# DAC.net
KiCad netlist of a schematic drawn in Altium Designer
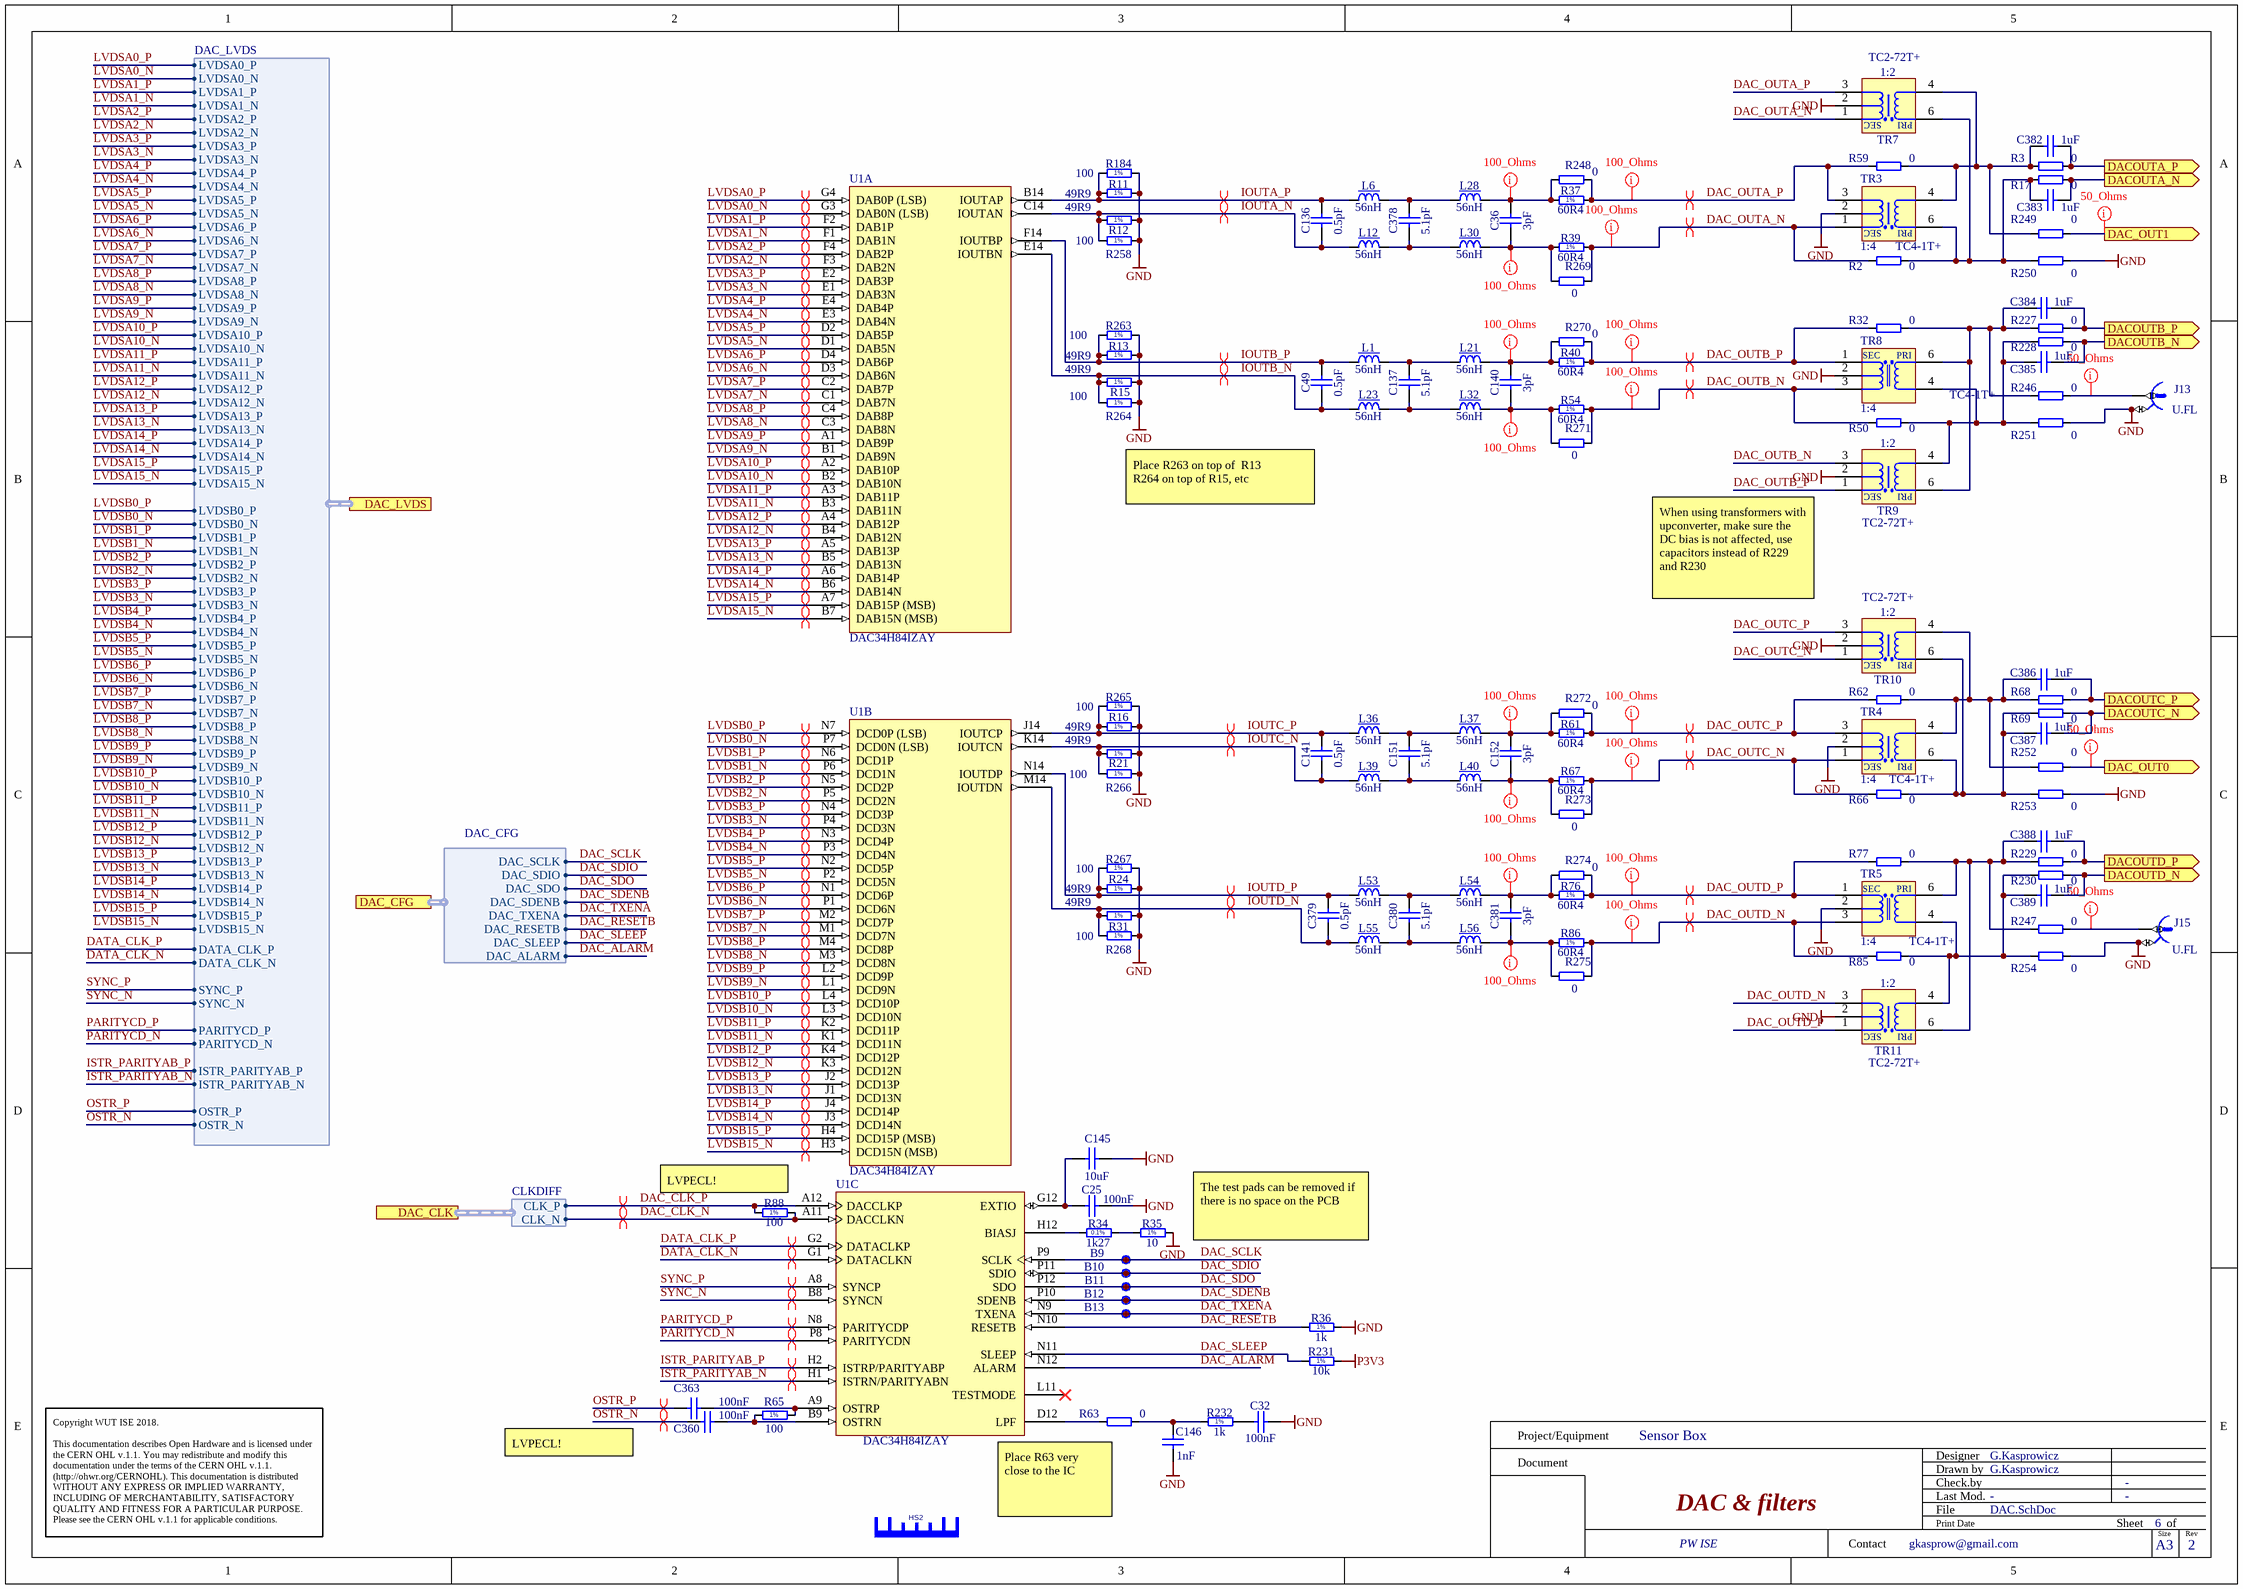
[diagram p0: DAC.SchDoc]

(export (version "E")
  (design (tool "Eeschema 10.0.6"))
  (components
    (comp (ref "B9")
      (value "SMD Pad")
      (footprint "C100")
      (description "Through Hole Pad")
      (fields (field (name "PART NUMBER") "SMD_PAD_D1MM") (field (name "AUTHOR") "CERN DEM JLC"))
      (libsource (lib "Eletro-mechanical") (part "Single SMD Pad (Round)"))
    )
    (comp (ref "B10")
      (value "SMD Pad")
      (footprint "C100")
      (description "Through Hole Pad")
      (fields (field (name "PART NUMBER") "SMD_PAD_D1MM") (field (name "AUTHOR") "CERN DEM JLC"))
      (libsource (lib "Eletro-mechanical") (part "Single SMD Pad (Round)"))
    )
    (comp (ref "B11")
      (value "SMD Pad")
      (footprint "C100")
      (description "Through Hole Pad")
      (fields (field (name "PART NUMBER") "SMD_PAD_D1MM") (field (name "AUTHOR") "CERN DEM JLC"))
      (libsource (lib "Eletro-mechanical") (part "Single SMD Pad (Round)"))
    )
    (comp (ref "B12")
      (value "SMD Pad")
      (footprint "C100")
      (description "Through Hole Pad")
      (fields (field (name "PART NUMBER") "SMD_PAD_D1MM") (field (name "AUTHOR") "CERN DEM JLC"))
      (libsource (lib "Eletro-mechanical") (part "Single SMD Pad (Round)"))
    )
    (comp (ref "B13")
      (value "SMD Pad")
      (footprint "C100")
      (description "Through Hole Pad")
      (fields (field (name "PART NUMBER") "SMD_PAD_D1MM") (field (name "AUTHOR") "CERN DEM JLC"))
      (libsource (lib "Eletro-mechanical") (part "Single SMD Pad (Round)"))
    )
    (comp (ref "C25")
      (value "100nF")
      (footprint "CAPC1005X55N")
      (description "Non-polarised capacitor")
      (fields
        (field (name "PART NUMBER") "CC0402_100NF_16V_10%_X5R")
        (field (name "VOLTAGE") "16V")
        (field (name "AUTHOR") "CERN DEM JLC")
      )
      (libsource (lib "Capacitors") (part "Capacitor - non polarized"))
    )
    (comp (ref "C32")
      (value "100nF")
      (footprint "CAPC1608X90N")
      (description "Non-polarised capacitor")
      (fields
        (field (name "PART NUMBER") "CC0603_100NF_100V_10%_X7R")
        (field (name "VOLTAGE") "100V")
        (field (name "AUTHOR") "CERN DEM JLC")
      )
      (libsource (lib "Capacitors") (part "Capacitor - non polarized"))
    )
    (comp (ref "C36")
      (value "3pF")
      (footprint "CAPC1608X87N")
      (description "Non-polarised capacitor")
      (libsource (lib "Capacitors") (part "CC0603_3pF_50V_0,1pF_NP0"))
    )
    (comp (ref "C49")
      (value "0.5pF")
      (footprint "CAPC1608X87N")
      (description "Non-polarised capacitor")
      (libsource (lib "Capacitors") (part "CC0603_0.5pF_50V_0,05pF_NP0"))
    )
    (comp (ref "C136")
      (value "0.5pF")
      (footprint "CAPC1608X87N")
      (description "Non-polarised capacitor")
      (libsource (lib "Capacitors") (part "CC0603_0.5pF_50V_0,05pF_NP0"))
    )
    (comp (ref "C137")
      (value "5.1pF")
      (footprint "CAPC1608X87N")
      (description "Non-polarised capacitor")
      (libsource (lib "Capacitors") (part "CC0603_5.1pF_50V_0.1pF_NP0"))
    )
    (comp (ref "C140")
      (value "3pF")
      (footprint "CAPC1608X87N")
      (description "Non-polarised capacitor")
      (libsource (lib "Capacitors") (part "CC0603_3pF_50V_0,1pF_NP0"))
    )
    (comp (ref "C141")
      (value "0.5pF")
      (footprint "CAPC1608X87N")
      (description "Non-polarised capacitor")
      (libsource (lib "Capacitors") (part "CC0603_0.5pF_50V_0,05pF_NP0"))
    )
    (comp (ref "C145")
      (value "10uF")
      (footprint "CAPC2012X95N")
      (description "Non-polarised capacitor")
      (fields
        (field (name "PART NUMBER") "CC0805_10UF_25V_10%_X5R")
        (field (name "VOLTAGE") "25V")
        (field (name "AUTHOR") "CERN DEM JLC")
      )
      (libsource (lib "Capacitors") (part "Capacitor - non polarized"))
    )
    (comp (ref "C146")
      (value "1nF")
      (footprint "CAPC1608X90N")
      (description "Non-polarised capacitor")
      (fields
        (field (name "PART NUMBER") "CC0603_1NF_50V_1%_NP0")
        (field (name "VOLTAGE") "50V")
        (field (name "AUTHOR") "CERN DEM JLC")
      )
      (libsource (lib "Capacitors") (part "Capacitor - non polarized"))
    )
    (comp (ref "C151")
      (value "5.1pF")
      (footprint "CAPC1608X87N")
      (description "Non-polarised capacitor")
      (libsource (lib "Capacitors") (part "CC0603_5.1pF_50V_0.1pF_NP0"))
    )
    (comp (ref "C152")
      (value "3pF")
      (footprint "CAPC1608X87N")
      (description "Non-polarised capacitor")
      (libsource (lib "Capacitors") (part "CC0603_3pF_50V_0,1pF_NP0"))
    )
    (comp (ref "C360")
      (value "100nF")
      (footprint "CAPC1005X55N")
      (description "Non-polarised capacitor")
      (fields
        (field (name "PART NUMBER") "CC0402_100NF_16V_10%_X5R")
        (field (name "VOLTAGE") "16V")
        (field (name "AUTHOR") "CERN DEM JLC")
      )
      (libsource (lib "Capacitors") (part "Capacitor - non polarized"))
    )
    (comp (ref "C363")
      (value "100nF")
      (footprint "CAPC1005X55N")
      (description "Non-polarised capacitor")
      (fields
        (field (name "PART NUMBER") "CC0402_100NF_16V_10%_X5R")
        (field (name "VOLTAGE") "16V")
        (field (name "AUTHOR") "CERN DEM JLC")
      )
      (libsource (lib "Capacitors") (part "Capacitor - non polarized"))
    )
    (comp (ref "C378")
      (value "5.1pF")
      (footprint "CAPC1608X87N")
      (description "Non-polarised capacitor")
      (libsource (lib "Capacitors") (part "CC0603_5.1pF_50V_0.1pF_NP0"))
    )
    (comp (ref "C379")
      (value "0.5pF")
      (footprint "CAPC1608X87N")
      (description "Non-polarised capacitor")
      (libsource (lib "Capacitors") (part "CC0603_0.5pF_50V_0,05pF_NP0"))
    )
    (comp (ref "C380")
      (value "5.1pF")
      (footprint "CAPC1608X87N")
      (description "Non-polarised capacitor")
      (libsource (lib "Capacitors") (part "CC0603_5.1pF_50V_0.1pF_NP0"))
    )
    (comp (ref "C381")
      (value "3pF")
      (footprint "CAPC1608X87N")
      (description "Non-polarised capacitor")
      (libsource (lib "Capacitors") (part "CC0603_3pF_50V_0,1pF_NP0"))
    )
    (comp (ref "C382")
      (value "1uF")
      (footprint "CAPC1005X55N")
      (description "Non-polarised capacitor")
      (fields
        (field (name "PART NUMBER") "CC0402_1UF_16V_10%_X5R")
        (field (name "VOLTAGE") "16V")
        (field (name "AUTHOR") "CERN DEM JLC")
      )
      (libsource (lib "Capacitors") (part "Capacitor - non polarized"))
    )
    (comp (ref "C383")
      (value "1uF")
      (footprint "CAPC1005X55N")
      (description "Non-polarised capacitor")
      (fields
        (field (name "PART NUMBER") "CC0402_1UF_16V_10%_X5R")
        (field (name "VOLTAGE") "16V")
        (field (name "AUTHOR") "CERN DEM JLC")
      )
      (libsource (lib "Capacitors") (part "Capacitor - non polarized"))
    )
    (comp (ref "C384")
      (value "1uF")
      (footprint "CAPC1005X55N")
      (description "Non-polarised capacitor")
      (fields
        (field (name "PART NUMBER") "CC0402_1UF_16V_10%_X5R")
        (field (name "VOLTAGE") "16V")
        (field (name "AUTHOR") "CERN DEM JLC")
      )
      (libsource (lib "Capacitors") (part "Capacitor - non polarized"))
    )
    (comp (ref "C385")
      (value "1uF")
      (footprint "CAPC1005X55N")
      (description "Non-polarised capacitor")
      (fields
        (field (name "PART NUMBER") "CC0402_1UF_16V_10%_X5R")
        (field (name "VOLTAGE") "16V")
        (field (name "AUTHOR") "CERN DEM JLC")
      )
      (libsource (lib "Capacitors") (part "Capacitor - non polarized"))
    )
    (comp (ref "C386")
      (value "1uF")
      (footprint "CAPC1005X55N")
      (description "Non-polarised capacitor")
      (fields
        (field (name "PART NUMBER") "CC0402_1UF_16V_10%_X5R")
        (field (name "VOLTAGE") "16V")
        (field (name "AUTHOR") "CERN DEM JLC")
      )
      (libsource (lib "Capacitors") (part "Capacitor - non polarized"))
    )
    (comp (ref "C387")
      (value "1uF")
      (footprint "CAPC1005X55N")
      (description "Non-polarised capacitor")
      (fields
        (field (name "PART NUMBER") "CC0402_1UF_16V_10%_X5R")
        (field (name "VOLTAGE") "16V")
        (field (name "AUTHOR") "CERN DEM JLC")
      )
      (libsource (lib "Capacitors") (part "Capacitor - non polarized"))
    )
    (comp (ref "C388")
      (value "1uF")
      (footprint "CAPC1005X55N")
      (description "Non-polarised capacitor")
      (fields
        (field (name "PART NUMBER") "CC0402_1UF_16V_10%_X5R")
        (field (name "VOLTAGE") "16V")
        (field (name "AUTHOR") "CERN DEM JLC")
      )
      (libsource (lib "Capacitors") (part "Capacitor - non polarized"))
    )
    (comp (ref "C389")
      (value "1uF")
      (footprint "CAPC1005X55N")
      (description "Non-polarised capacitor")
      (fields
        (field (name "PART NUMBER") "CC0402_1UF_16V_10%_X5R")
        (field (name "VOLTAGE") "16V")
        (field (name "AUTHOR") "CERN DEM JLC")
      )
      (libsource (lib "Capacitors") (part "Capacitor - non polarized"))
    )
    (comp (ref "HS2")
      (value "Heat Sink No Pad")
      (footprint "HSINK_HSB03-121218")
      (description "Rth: 27.5K/W - L 12mm x W 12mm x H 18mm Black Anodized Heatsinks for BGA")
      (fields
        (field (name "PART NUMBER") "HSB03-121218")
        (field (name "MANUFACTURER") "CUI")
        (field (name "AUTHOR") "GK")
      )
      (libsource (lib "Mechanical") (part "HEAT_SINK_BGA_12x12x18"))
    )
    (comp (ref "J13")
      (value "U.FL")
      (footprint "HIROSE_U.FL-R-SMT-1(10)")
      (fields
        (field (name "MANUFACTURER") "HIROSE (HRS)")
        (field (name "MANUFACTURER PART NUMBER") "U.FL-R-SMT-1(10)")
        (field (name "PART NUMBER") "HIROSE_U.FL-R-SMT-1(10)")
        (field (name "AUTHOR") "CERN DEM JLC")
      )
      (libsource (lib "Connectors") (part "Coax_1Male_1Shield"))
    )
    (comp (ref "J15")
      (value "U.FL")
      (footprint "HIROSE_U.FL-R-SMT-1(10)")
      (fields
        (field (name "MANUFACTURER") "HIROSE (HRS)")
        (field (name "MANUFACTURER PART NUMBER") "U.FL-R-SMT-1(10)")
        (field (name "PART NUMBER") "HIROSE_U.FL-R-SMT-1(10)")
        (field (name "AUTHOR") "CERN DEM JLC")
      )
      (libsource (lib "Connectors") (part "Coax_1Male_1Shield"))
    )
    (comp (ref "L1")
      (value "56nH")
      (footprint "IND_MURATA_LQW18AS_0Z")
      (description "Inductor With Core")
      (fields
        (field (name "PART NUMBER") "IND0603_56NH_2%_MURATA_LQW18AS56NG0ZD")
        (field (name "POWER") "600mA")
        (field (name "AUTHOR") "CERN DEM BC")
      )
      (libsource (lib "Inductors & Transformers") (part "Inductor With Magnetic core"))
    )
    (comp (ref "L6")
      (value "56nH")
      (footprint "IND_MURATA_LQW18AS_0Z")
      (description "Inductor With Core")
      (fields
        (field (name "PART NUMBER") "IND0603_56NH_2%_MURATA_LQW18AS56NG0ZD")
        (field (name "POWER") "600mA")
        (field (name "AUTHOR") "CERN DEM BC")
      )
      (libsource (lib "Inductors & Transformers") (part "Inductor With Magnetic core"))
    )
    (comp (ref "L12")
      (value "56nH")
      (footprint "IND_MURATA_LQW18AS_0Z")
      (description "Inductor With Core")
      (fields
        (field (name "PART NUMBER") "IND0603_56NH_2%_MURATA_LQW18AS56NG0ZD")
        (field (name "POWER") "600mA")
        (field (name "AUTHOR") "CERN DEM BC")
      )
      (libsource (lib "Inductors & Transformers") (part "Inductor With Magnetic core"))
    )
    (comp (ref "L21")
      (value "56nH")
      (footprint "IND_MURATA_LQW18AS_0Z")
      (description "Inductor With Core")
      (fields
        (field (name "PART NUMBER") "IND0603_56NH_2%_MURATA_LQW18AS56NG0ZD")
        (field (name "POWER") "600mA")
        (field (name "AUTHOR") "CERN DEM BC")
      )
      (libsource (lib "Inductors & Transformers") (part "Inductor With Magnetic core"))
    )
    (comp (ref "L23")
      (value "56nH")
      (footprint "IND_MURATA_LQW18AS_0Z")
      (description "Inductor With Core")
      (fields
        (field (name "PART NUMBER") "IND0603_56NH_2%_MURATA_LQW18AS56NG0ZD")
        (field (name "POWER") "600mA")
        (field (name "AUTHOR") "CERN DEM BC")
      )
      (libsource (lib "Inductors & Transformers") (part "Inductor With Magnetic core"))
    )
    (comp (ref "L28")
      (value "56nH")
      (footprint "IND_MURATA_LQW18AS_0Z")
      (description "Inductor With Core")
      (fields
        (field (name "PART NUMBER") "IND0603_56NH_2%_MURATA_LQW18AS56NG0ZD")
        (field (name "POWER") "600mA")
        (field (name "AUTHOR") "CERN DEM BC")
      )
      (libsource (lib "Inductors & Transformers") (part "Inductor With Magnetic core"))
    )
    (comp (ref "L30")
      (value "56nH")
      (footprint "IND_MURATA_LQW18AS_0Z")
      (description "Inductor With Core")
      (fields
        (field (name "PART NUMBER") "IND0603_56NH_2%_MURATA_LQW18AS56NG0ZD")
        (field (name "POWER") "600mA")
        (field (name "AUTHOR") "CERN DEM BC")
      )
      (libsource (lib "Inductors & Transformers") (part "Inductor With Magnetic core"))
    )
    (comp (ref "L32")
      (value "56nH")
      (footprint "IND_MURATA_LQW18AS_0Z")
      (description "Inductor With Core")
      (fields
        (field (name "PART NUMBER") "IND0603_56NH_2%_MURATA_LQW18AS56NG0ZD")
        (field (name "POWER") "600mA")
        (field (name "AUTHOR") "CERN DEM BC")
      )
      (libsource (lib "Inductors & Transformers") (part "Inductor With Magnetic core"))
    )
    (comp (ref "L36")
      (value "56nH")
      (footprint "IND_MURATA_LQW18AS_0Z")
      (description "Inductor With Core")
      (fields
        (field (name "PART NUMBER") "IND0603_56NH_2%_MURATA_LQW18AS56NG0ZD")
        (field (name "POWER") "600mA")
        (field (name "AUTHOR") "CERN DEM BC")
      )
      (libsource (lib "Inductors & Transformers") (part "Inductor With Magnetic core"))
    )
    (comp (ref "L37")
      (value "56nH")
      (footprint "IND_MURATA_LQW18AS_0Z")
      (description "Inductor With Core")
      (fields
        (field (name "PART NUMBER") "IND0603_56NH_2%_MURATA_LQW18AS56NG0ZD")
        (field (name "POWER") "600mA")
        (field (name "AUTHOR") "CERN DEM BC")
      )
      (libsource (lib "Inductors & Transformers") (part "Inductor With Magnetic core"))
    )
    (comp (ref "L39")
      (value "56nH")
      (footprint "IND_MURATA_LQW18AS_0Z")
      (description "Inductor With Core")
      (fields
        (field (name "PART NUMBER") "IND0603_56NH_2%_MURATA_LQW18AS56NG0ZD")
        (field (name "POWER") "600mA")
        (field (name "AUTHOR") "CERN DEM BC")
      )
      (libsource (lib "Inductors & Transformers") (part "Inductor With Magnetic core"))
    )
    (comp (ref "L40")
      (value "56nH")
      (footprint "IND_MURATA_LQW18AS_0Z")
      (description "Inductor With Core")
      (fields
        (field (name "PART NUMBER") "IND0603_56NH_2%_MURATA_LQW18AS56NG0ZD")
        (field (name "POWER") "600mA")
        (field (name "AUTHOR") "CERN DEM BC")
      )
      (libsource (lib "Inductors & Transformers") (part "Inductor With Magnetic core"))
    )
    (comp (ref "L53")
      (value "56nH")
      (footprint "IND_MURATA_LQW18AS_0Z")
      (description "Inductor With Core")
      (fields
        (field (name "PART NUMBER") "IND0603_56NH_2%_MURATA_LQW18AS56NG0ZD")
        (field (name "POWER") "600mA")
        (field (name "AUTHOR") "CERN DEM BC")
      )
      (libsource (lib "Inductors & Transformers") (part "Inductor With Magnetic core"))
    )
    (comp (ref "L54")
      (value "56nH")
      (footprint "IND_MURATA_LQW18AS_0Z")
      (description "Inductor With Core")
      (fields
        (field (name "PART NUMBER") "IND0603_56NH_2%_MURATA_LQW18AS56NG0ZD")
        (field (name "POWER") "600mA")
        (field (name "AUTHOR") "CERN DEM BC")
      )
      (libsource (lib "Inductors & Transformers") (part "Inductor With Magnetic core"))
    )
    (comp (ref "L55")
      (value "56nH")
      (footprint "IND_MURATA_LQW18AS_0Z")
      (description "Inductor With Core")
      (fields
        (field (name "PART NUMBER") "IND0603_56NH_2%_MURATA_LQW18AS56NG0ZD")
        (field (name "POWER") "600mA")
        (field (name "AUTHOR") "CERN DEM BC")
      )
      (libsource (lib "Inductors & Transformers") (part "Inductor With Magnetic core"))
    )
    (comp (ref "L56")
      (value "56nH")
      (footprint "IND_MURATA_LQW18AS_0Z")
      (description "Inductor With Core")
      (fields
        (field (name "PART NUMBER") "IND0603_56NH_2%_MURATA_LQW18AS56NG0ZD")
        (field (name "POWER") "600mA")
        (field (name "AUTHOR") "CERN DEM BC")
      )
      (libsource (lib "Inductors & Transformers") (part "Inductor With Magnetic core"))
    )
    (comp (ref "R2")
      (value "0")
      (footprint "RESC1005X40N")
      (description "Resistor")
      (fields
        (field (name "PART NUMBER") "R0402_0R_JUMPER")
        (field (name "MANUFACTURER") "GENERIC")
        (field (name "AUTHOR") "CERN DEM JLC")
      )
      (libsource (lib "Resistors") (part "Resistor"))
    )
    (comp (ref "R3")
      (value "0")
      (footprint "RESC1005X40N")
      (description "Resistor")
      (fields
        (field (name "PART NUMBER") "R0402_0R_JUMPER")
        (field (name "MANUFACTURER") "GENERIC")
        (field (name "AUTHOR") "CERN DEM JLC")
      )
      (libsource (lib "Resistors") (part "Resistor"))
    )
    (comp (ref "R11")
      (value "49R9")
      (footprint "RESC1005X40N")
      (description "Resistor - 1%")
      (fields
        (field (name "PART NUMBER") "R0402_49R9_1%_0.0625W_100PPM")
        (field (name "POWER") "0.0625W")
        (field (name "AUTHOR") "CERN DEM JLC")
      )
      (libsource (lib "Resistors") (part "Resistor - 1%"))
    )
    (comp (ref "R12")
      (value "49R9")
      (footprint "RESC1005X40N")
      (description "Resistor - 1%")
      (fields
        (field (name "PART NUMBER") "R0402_49R9_1%_0.0625W_100PPM")
        (field (name "POWER") "0.0625W")
        (field (name "AUTHOR") "CERN DEM JLC")
      )
      (libsource (lib "Resistors") (part "Resistor - 1%"))
    )
    (comp (ref "R13")
      (value "49R9")
      (footprint "RESC1005X40N")
      (description "Resistor - 1%")
      (fields
        (field (name "PART NUMBER") "R0402_49R9_1%_0.0625W_100PPM")
        (field (name "POWER") "0.0625W")
        (field (name "AUTHOR") "CERN DEM JLC")
      )
      (libsource (lib "Resistors") (part "Resistor - 1%"))
    )
    (comp (ref "R15")
      (value "49R9")
      (footprint "RESC1005X40N")
      (description "Resistor - 1%")
      (fields
        (field (name "PART NUMBER") "R0402_49R9_1%_0.0625W_100PPM")
        (field (name "POWER") "0.0625W")
        (field (name "AUTHOR") "CERN DEM JLC")
      )
      (libsource (lib "Resistors") (part "Resistor - 1%"))
    )
    (comp (ref "R16")
      (value "49R9")
      (footprint "RESC1005X40N")
      (description "Resistor - 1%")
      (fields
        (field (name "PART NUMBER") "R0402_49R9_1%_0.0625W_100PPM")
        (field (name "POWER") "0.0625W")
        (field (name "AUTHOR") "CERN DEM JLC")
      )
      (libsource (lib "Resistors") (part "Resistor - 1%"))
    )
    (comp (ref "R17")
      (value "0")
      (footprint "RESC1005X40N")
      (description "Resistor")
      (fields
        (field (name "PART NUMBER") "R0402_0R_JUMPER")
        (field (name "MANUFACTURER") "GENERIC")
        (field (name "AUTHOR") "CERN DEM JLC")
      )
      (libsource (lib "Resistors") (part "Resistor"))
    )
    (comp (ref "R21")
      (value "49R9")
      (footprint "RESC1005X40N")
      (description "Resistor - 1%")
      (fields
        (field (name "PART NUMBER") "R0402_49R9_1%_0.0625W_100PPM")
        (field (name "POWER") "0.0625W")
        (field (name "AUTHOR") "CERN DEM JLC")
      )
      (libsource (lib "Resistors") (part "Resistor - 1%"))
    )
    (comp (ref "R24")
      (value "49R9")
      (footprint "RESC1005X40N")
      (description "Resistor - 1%")
      (fields
        (field (name "PART NUMBER") "R0402_49R9_1%_0.0625W_100PPM")
        (field (name "POWER") "0.0625W")
        (field (name "AUTHOR") "CERN DEM JLC")
      )
      (libsource (lib "Resistors") (part "Resistor - 1%"))
    )
    (comp (ref "R31")
      (value "49R9")
      (footprint "RESC1005X40N")
      (description "Resistor - 1%")
      (fields
        (field (name "PART NUMBER") "R0402_49R9_1%_0.0625W_100PPM")
        (field (name "POWER") "0.0625W")
        (field (name "AUTHOR") "CERN DEM JLC")
      )
      (libsource (lib "Resistors") (part "Resistor - 1%"))
    )
    (comp (ref "R32")
      (value "0")
      (footprint "RESC1005X40N")
      (description "Resistor")
      (fields
        (field (name "PART NUMBER") "R0402_0R_JUMPER")
        (field (name "MANUFACTURER") "GENERIC")
        (field (name "AUTHOR") "CERN DEM JLC")
      )
      (libsource (lib "Resistors") (part "Resistor"))
    )
    (comp (ref "R34")
      (value "1k27")
      (footprint "RESC1608X55N")
      (description "Resistor - 0.1%")
      (fields
        (field (name "PART NUMBER") "R0603_1K27_0.1%_0.063W_10PPM")
        (field (name "POWER") "0.063W")
        (field (name "AUTHOR") "CERN DEM JLC")
      )
      (libsource (lib "Resistors") (part "Resistor - 0.1%"))
    )
    (comp (ref "R35")
      (value "10")
      (footprint "RESC1005X40N")
      (description "Resistor - 1%")
      (fields
        (field (name "PART NUMBER") "R0402_10R_1%_0.0625W_200PPM")
        (field (name "POWER") "0.0625W")
        (field (name "AUTHOR") "CERN DEM JLC")
      )
      (libsource (lib "Resistors") (part "Resistor - 1%"))
    )
    (comp (ref "R36")
      (value "1k")
      (footprint "RESC1608X55N")
      (description "Resistor - 1%")
      (fields
        (field (name "PART NUMBER") "R0603_1K_1%_0.1W_100PPM")
        (field (name "POWER") "0.1W")
        (field (name "AUTHOR") "CERN DEM JLC")
      )
      (libsource (lib "Resistors") (part "Resistor - 1%"))
    )
    (comp (ref "R37")
      (value "60R4")
      (footprint "RESC1005X40N")
      (description "Resistor - 1%")
      (fields
        (field (name "PART NUMBER") "R0402_60R4_1%_0.0625W_100PPM")
        (field (name "POWER") "0.0625W")
        (field (name "AUTHOR") "GK")
      )
      (libsource (lib "Passives_RC") (part "R0402_60R4_1%_0.0625W_100PPM"))
    )
    (comp (ref "R39")
      (value "60R4")
      (footprint "RESC1005X40N")
      (description "Resistor - 1%")
      (fields
        (field (name "PART NUMBER") "R0402_60R4_1%_0.0625W_100PPM")
        (field (name "POWER") "0.0625W")
        (field (name "AUTHOR") "GK")
      )
      (libsource (lib "Passives_RC") (part "R0402_60R4_1%_0.0625W_100PPM"))
    )
    (comp (ref "R40")
      (value "60R4")
      (footprint "RESC1005X40N")
      (description "Resistor - 1%")
      (fields
        (field (name "PART NUMBER") "R0402_60R4_1%_0.0625W_100PPM")
        (field (name "POWER") "0.0625W")
        (field (name "AUTHOR") "GK")
      )
      (libsource (lib "Passives_RC") (part "R0402_60R4_1%_0.0625W_100PPM"))
    )
    (comp (ref "R50")
      (value "0")
      (footprint "RESC1005X40N")
      (description "Resistor")
      (fields
        (field (name "PART NUMBER") "R0402_0R_JUMPER")
        (field (name "MANUFACTURER") "GENERIC")
        (field (name "AUTHOR") "CERN DEM JLC")
      )
      (libsource (lib "Resistors") (part "Resistor"))
    )
    (comp (ref "R54")
      (value "60R4")
      (footprint "RESC1005X40N")
      (description "Resistor - 1%")
      (fields
        (field (name "PART NUMBER") "R0402_60R4_1%_0.0625W_100PPM")
        (field (name "POWER") "0.0625W")
        (field (name "AUTHOR") "GK")
      )
      (libsource (lib "Passives_RC") (part "R0402_60R4_1%_0.0625W_100PPM"))
    )
    (comp (ref "R59")
      (value "0")
      (footprint "RESC1005X40N")
      (description "Resistor")
      (fields
        (field (name "PART NUMBER") "R0402_0R_JUMPER")
        (field (name "MANUFACTURER") "GENERIC")
        (field (name "AUTHOR") "CERN DEM JLC")
      )
      (libsource (lib "Resistors") (part "Resistor"))
    )
    (comp (ref "R61")
      (value "60R4")
      (footprint "RESC1005X40N")
      (description "Resistor - 1%")
      (fields
        (field (name "PART NUMBER") "R0402_60R4_1%_0.0625W_100PPM")
        (field (name "POWER") "0.0625W")
        (field (name "AUTHOR") "GK")
      )
      (libsource (lib "Passives_RC") (part "R0402_60R4_1%_0.0625W_100PPM"))
    )
    (comp (ref "R62")
      (value "0")
      (footprint "RESC1005X40N")
      (description "Resistor")
      (fields
        (field (name "PART NUMBER") "R0402_0R_JUMPER")
        (field (name "MANUFACTURER") "GENERIC")
        (field (name "AUTHOR") "CERN DEM JLC")
      )
      (libsource (lib "Resistors") (part "Resistor"))
    )
    (comp (ref "R63")
      (value "0")
      (footprint "RESC1005X40N")
      (description "Resistor")
      (fields
        (field (name "PART NUMBER") "R0402_0R_JUMPER")
        (field (name "MANUFACTURER") "GENERIC")
        (field (name "AUTHOR") "CERN DEM JLC")
      )
      (libsource (lib "Resistors") (part "Resistor"))
    )
    (comp (ref "R65")
      (value "100")
      (footprint "RESC0603X28N")
      (description "Resistor - 1%")
      (fields
        (field (name "PART NUMBER") "R0201_100R_1%_0.05W_200PPM")
        (field (name "POWER") "0.05W")
        (field (name "AUTHOR") "CERN DEM JLC")
      )
      (libsource (lib "Resistors") (part "Resistor - 1%"))
    )
    (comp (ref "R66")
      (value "0")
      (footprint "RESC1005X40N")
      (description "Resistor")
      (fields
        (field (name "PART NUMBER") "R0402_0R_JUMPER")
        (field (name "MANUFACTURER") "GENERIC")
        (field (name "AUTHOR") "CERN DEM JLC")
      )
      (libsource (lib "Resistors") (part "Resistor"))
    )
    (comp (ref "R67")
      (value "60R4")
      (footprint "RESC1005X40N")
      (description "Resistor - 1%")
      (fields
        (field (name "PART NUMBER") "R0402_60R4_1%_0.0625W_100PPM")
        (field (name "POWER") "0.0625W")
        (field (name "AUTHOR") "GK")
      )
      (libsource (lib "Passives_RC") (part "R0402_60R4_1%_0.0625W_100PPM"))
    )
    (comp (ref "R68")
      (value "0")
      (footprint "RESC1005X40N")
      (description "Resistor")
      (fields
        (field (name "PART NUMBER") "R0402_0R_JUMPER")
        (field (name "MANUFACTURER") "GENERIC")
        (field (name "AUTHOR") "CERN DEM JLC")
      )
      (libsource (lib "Resistors") (part "Resistor"))
    )
    (comp (ref "R69")
      (value "0")
      (footprint "RESC1005X40N")
      (description "Resistor")
      (fields
        (field (name "PART NUMBER") "R0402_0R_JUMPER")
        (field (name "MANUFACTURER") "GENERIC")
        (field (name "AUTHOR") "CERN DEM JLC")
      )
      (libsource (lib "Resistors") (part "Resistor"))
    )
    (comp (ref "R76")
      (value "60R4")
      (footprint "RESC1005X40N")
      (description "Resistor - 1%")
      (fields
        (field (name "PART NUMBER") "R0402_60R4_1%_0.0625W_100PPM")
        (field (name "POWER") "0.0625W")
        (field (name "AUTHOR") "GK")
      )
      (libsource (lib "Passives_RC") (part "R0402_60R4_1%_0.0625W_100PPM"))
    )
    (comp (ref "R77")
      (value "0")
      (footprint "RESC1005X40N")
      (description "Resistor")
      (fields
        (field (name "PART NUMBER") "R0402_0R_JUMPER")
        (field (name "MANUFACTURER") "GENERIC")
        (field (name "AUTHOR") "CERN DEM JLC")
      )
      (libsource (lib "Resistors") (part "Resistor"))
    )
    (comp (ref "R85")
      (value "0")
      (footprint "RESC1005X40N")
      (description "Resistor")
      (fields
        (field (name "PART NUMBER") "R0402_0R_JUMPER")
        (field (name "MANUFACTURER") "GENERIC")
        (field (name "AUTHOR") "CERN DEM JLC")
      )
      (libsource (lib "Resistors") (part "Resistor"))
    )
    (comp (ref "R86")
      (value "60R4")
      (footprint "RESC1005X40N")
      (description "Resistor - 1%")
      (fields
        (field (name "PART NUMBER") "R0402_60R4_1%_0.0625W_100PPM")
        (field (name "POWER") "0.0625W")
        (field (name "AUTHOR") "GK")
      )
      (libsource (lib "Passives_RC") (part "R0402_60R4_1%_0.0625W_100PPM"))
    )
    (comp (ref "R88")
      (value "100")
      (footprint "RESC0603X28N")
      (description "Resistor - 1%")
      (fields
        (field (name "PART NUMBER") "R0201_100R_1%_0.05W_200PPM")
        (field (name "POWER") "0.05W")
        (field (name "AUTHOR") "CERN DEM JLC")
      )
      (libsource (lib "Resistors") (part "Resistor - 1%"))
    )
    (comp (ref "R184")
      (value "100")
      (footprint "RESC1005X40N")
      (description "Resistor - 1%")
      (fields
        (field (name "PART NUMBER") "R0402_100R_1%_0.1W_100PPM")
        (field (name "POWER") "0.1W")
        (field (name "AUTHOR") "CERN DEM JLC")
      )
      (libsource (lib "Resistors") (part "Resistor - 1%"))
    )
    (comp (ref "R227")
      (value "0")
      (footprint "RESC1005X40N")
      (description "Resistor")
      (fields
        (field (name "PART NUMBER") "R0402_0R_JUMPER")
        (field (name "MANUFACTURER") "GENERIC")
        (field (name "AUTHOR") "CERN DEM JLC")
      )
      (libsource (lib "Resistors") (part "Resistor"))
    )
    (comp (ref "R228")
      (value "0")
      (footprint "RESC1005X40N")
      (description "Resistor")
      (fields
        (field (name "PART NUMBER") "R0402_0R_JUMPER")
        (field (name "MANUFACTURER") "GENERIC")
        (field (name "AUTHOR") "CERN DEM JLC")
      )
      (libsource (lib "Resistors") (part "Resistor"))
    )
    (comp (ref "R229")
      (value "0")
      (footprint "RESC1005X40N")
      (description "Resistor")
      (fields
        (field (name "PART NUMBER") "R0402_0R_JUMPER")
        (field (name "MANUFACTURER") "GENERIC")
        (field (name "AUTHOR") "CERN DEM JLC")
      )
      (libsource (lib "Resistors") (part "Resistor"))
    )
    (comp (ref "R230")
      (value "0")
      (footprint "RESC1005X40N")
      (description "Resistor")
      (fields
        (field (name "PART NUMBER") "R0402_0R_JUMPER")
        (field (name "MANUFACTURER") "GENERIC")
        (field (name "AUTHOR") "CERN DEM JLC")
      )
      (libsource (lib "Resistors") (part "Resistor"))
    )
    (comp (ref "R231")
      (value "10k")
      (footprint "RESC1608X55N")
      (description "Resistor - 1%")
      (fields
        (field (name "PART NUMBER") "R0603_10K_1%_0.1W_100PPM")
        (field (name "POWER") "0.1W")
        (field (name "AUTHOR") "CERN DEM JLC")
      )
      (libsource (lib "Resistors") (part "Resistor - 1%"))
    )
    (comp (ref "R232")
      (value "1k")
      (footprint "RESC1608X55N")
      (description "Resistor - 1%")
      (fields
        (field (name "PART NUMBER") "R0603_1K_1%_0.1W_100PPM")
        (field (name "POWER") "0.1W")
        (field (name "AUTHOR") "CERN DEM JLC")
      )
      (libsource (lib "Resistors") (part "Resistor - 1%"))
    )
    (comp (ref "R246")
      (value "0")
      (footprint "RESC1005X40N")
      (description "Resistor")
      (fields
        (field (name "PART NUMBER") "R0402_0R_JUMPER")
        (field (name "MANUFACTURER") "GENERIC")
        (field (name "AUTHOR") "CERN DEM JLC")
      )
      (libsource (lib "Resistors") (part "Resistor"))
    )
    (comp (ref "R247")
      (value "0")
      (footprint "RESC1005X40N")
      (description "Resistor")
      (fields
        (field (name "PART NUMBER") "R0402_0R_JUMPER")
        (field (name "MANUFACTURER") "GENERIC")
        (field (name "AUTHOR") "CERN DEM JLC")
      )
      (libsource (lib "Resistors") (part "Resistor"))
    )
    (comp (ref "R248")
      (value "0")
      (footprint "RESC1005X40N")
      (description "Resistor")
      (fields
        (field (name "PART NUMBER") "R0402_0R_JUMPER")
        (field (name "MANUFACTURER") "GENERIC")
        (field (name "AUTHOR") "CERN DEM JLC")
      )
      (libsource (lib "Resistors") (part "Resistor"))
    )
    (comp (ref "R249")
      (value "0")
      (footprint "RESC1005X40N")
      (description "Resistor")
      (fields
        (field (name "PART NUMBER") "R0402_0R_JUMPER")
        (field (name "MANUFACTURER") "GENERIC")
        (field (name "AUTHOR") "CERN DEM JLC")
      )
      (libsource (lib "Resistors") (part "Resistor"))
    )
    (comp (ref "R250")
      (value "0")
      (footprint "RESC1005X40N")
      (description "Resistor")
      (fields
        (field (name "PART NUMBER") "R0402_0R_JUMPER")
        (field (name "MANUFACTURER") "GENERIC")
        (field (name "AUTHOR") "CERN DEM JLC")
      )
      (libsource (lib "Resistors") (part "Resistor"))
    )
    (comp (ref "R251")
      (value "0")
      (footprint "RESC1005X40N")
      (description "Resistor")
      (fields
        (field (name "PART NUMBER") "R0402_0R_JUMPER")
        (field (name "MANUFACTURER") "GENERIC")
        (field (name "AUTHOR") "CERN DEM JLC")
      )
      (libsource (lib "Resistors") (part "Resistor"))
    )
    (comp (ref "R252")
      (value "0")
      (footprint "RESC1005X40N")
      (description "Resistor")
      (fields
        (field (name "PART NUMBER") "R0402_0R_JUMPER")
        (field (name "MANUFACTURER") "GENERIC")
        (field (name "AUTHOR") "CERN DEM JLC")
      )
      (libsource (lib "Resistors") (part "Resistor"))
    )
    (comp (ref "R253")
      (value "0")
      (footprint "RESC1005X40N")
      (description "Resistor")
      (fields
        (field (name "PART NUMBER") "R0402_0R_JUMPER")
        (field (name "MANUFACTURER") "GENERIC")
        (field (name "AUTHOR") "CERN DEM JLC")
      )
      (libsource (lib "Resistors") (part "Resistor"))
    )
    (comp (ref "R254")
      (value "0")
      (footprint "RESC1005X40N")
      (description "Resistor")
      (fields
        (field (name "PART NUMBER") "R0402_0R_JUMPER")
        (field (name "MANUFACTURER") "GENERIC")
        (field (name "AUTHOR") "CERN DEM JLC")
      )
      (libsource (lib "Resistors") (part "Resistor"))
    )
    (comp (ref "R258")
      (value "100")
      (footprint "RESC1005X40N")
      (description "Resistor - 1%")
      (fields
        (field (name "PART NUMBER") "R0402_100R_1%_0.1W_100PPM")
        (field (name "POWER") "0.1W")
        (field (name "AUTHOR") "CERN DEM JLC")
      )
      (libsource (lib "Resistors") (part "Resistor - 1%"))
    )
    (comp (ref "R263")
      (value "100")
      (footprint "RESC1005X40N")
      (description "Resistor - 1%")
      (fields
        (field (name "PART NUMBER") "R0402_100R_1%_0.1W_100PPM")
        (field (name "POWER") "0.1W")
        (field (name "AUTHOR") "CERN DEM JLC")
      )
      (libsource (lib "Resistors") (part "Resistor - 1%"))
    )
    (comp (ref "R264")
      (value "100")
      (footprint "RESC1005X40N")
      (description "Resistor - 1%")
      (fields
        (field (name "PART NUMBER") "R0402_100R_1%_0.1W_100PPM")
        (field (name "POWER") "0.1W")
        (field (name "AUTHOR") "CERN DEM JLC")
      )
      (libsource (lib "Resistors") (part "Resistor - 1%"))
    )
    (comp (ref "R265")
      (value "100")
      (footprint "RESC1005X40N")
      (description "Resistor - 1%")
      (fields
        (field (name "PART NUMBER") "R0402_100R_1%_0.1W_100PPM")
        (field (name "POWER") "0.1W")
        (field (name "AUTHOR") "CERN DEM JLC")
      )
      (libsource (lib "Resistors") (part "Resistor - 1%"))
    )
    (comp (ref "R266")
      (value "100")
      (footprint "RESC1005X40N")
      (description "Resistor - 1%")
      (fields
        (field (name "PART NUMBER") "R0402_100R_1%_0.1W_100PPM")
        (field (name "POWER") "0.1W")
        (field (name "AUTHOR") "CERN DEM JLC")
      )
      (libsource (lib "Resistors") (part "Resistor - 1%"))
    )
    (comp (ref "R267")
      (value "100")
      (footprint "RESC1005X40N")
      (description "Resistor - 1%")
      (fields
        (field (name "PART NUMBER") "R0402_100R_1%_0.1W_100PPM")
        (field (name "POWER") "0.1W")
        (field (name "AUTHOR") "CERN DEM JLC")
      )
      (libsource (lib "Resistors") (part "Resistor - 1%"))
    )
    (comp (ref "R268")
      (value "100")
      (footprint "RESC1005X40N")
      (description "Resistor - 1%")
      (fields
        (field (name "PART NUMBER") "R0402_100R_1%_0.1W_100PPM")
        (field (name "POWER") "0.1W")
        (field (name "AUTHOR") "CERN DEM JLC")
      )
      (libsource (lib "Resistors") (part "Resistor - 1%"))
    )
    (comp (ref "R269")
      (value "0")
      (footprint "RESC1005X40N")
      (description "Resistor")
      (fields
        (field (name "PART NUMBER") "R0402_0R_JUMPER")
        (field (name "MANUFACTURER") "GENERIC")
        (field (name "AUTHOR") "CERN DEM JLC")
      )
      (libsource (lib "Resistors") (part "Resistor"))
    )
    (comp (ref "R270")
      (value "0")
      (footprint "RESC1005X40N")
      (description "Resistor")
      (fields
        (field (name "PART NUMBER") "R0402_0R_JUMPER")
        (field (name "MANUFACTURER") "GENERIC")
        (field (name "AUTHOR") "CERN DEM JLC")
      )
      (libsource (lib "Resistors") (part "Resistor"))
    )
    (comp (ref "R271")
      (value "0")
      (footprint "RESC1005X40N")
      (description "Resistor")
      (fields
        (field (name "PART NUMBER") "R0402_0R_JUMPER")
        (field (name "MANUFACTURER") "GENERIC")
        (field (name "AUTHOR") "CERN DEM JLC")
      )
      (libsource (lib "Resistors") (part "Resistor"))
    )
    (comp (ref "R272")
      (value "0")
      (footprint "RESC1005X40N")
      (description "Resistor")
      (fields
        (field (name "PART NUMBER") "R0402_0R_JUMPER")
        (field (name "MANUFACTURER") "GENERIC")
        (field (name "AUTHOR") "CERN DEM JLC")
      )
      (libsource (lib "Resistors") (part "Resistor"))
    )
    (comp (ref "R273")
      (value "0")
      (footprint "RESC1005X40N")
      (description "Resistor")
      (fields
        (field (name "PART NUMBER") "R0402_0R_JUMPER")
        (field (name "MANUFACTURER") "GENERIC")
        (field (name "AUTHOR") "CERN DEM JLC")
      )
      (libsource (lib "Resistors") (part "Resistor"))
    )
    (comp (ref "R274")
      (value "0")
      (footprint "RESC1005X40N")
      (description "Resistor")
      (fields
        (field (name "PART NUMBER") "R0402_0R_JUMPER")
        (field (name "MANUFACTURER") "GENERIC")
        (field (name "AUTHOR") "CERN DEM JLC")
      )
      (libsource (lib "Resistors") (part "Resistor"))
    )
    (comp (ref "R275")
      (value "0")
      (footprint "RESC1005X40N")
      (description "Resistor")
      (fields
        (field (name "PART NUMBER") "R0402_0R_JUMPER")
        (field (name "MANUFACTURER") "GENERIC")
        (field (name "AUTHOR") "CERN DEM JLC")
      )
      (libsource (lib "Resistors") (part "Resistor"))
    )
    (comp (ref "TR3")
      (value "1:4")
      (footprint "XFMR_MINI-CIRCUITS_AT224")
      (description "50 Ohms 0.5 to 300 MHz RF Transformer")
      (fields
        (field (name "PART NUMBER") "XFMR_MINI-CIRCUITS_TC4-1T+")
        (field (name "MANUFACTURER") "MINI-CIRCUITS")
        (field (name "MANUFACTURER PART NUMBER") "TC4-1T+")
        (field (name "AUTHOR") "GK")
      )
      (libsource (lib "") (part "XFMR_MINI-CIRCUITS_TC4-1T+_1"))
    )
    (comp (ref "TR4")
      (value "1:4")
      (footprint "XFMR_MINI-CIRCUITS_AT224")
      (description "50 Ohms 0.5 to 300 MHz RF Transformer")
      (fields
        (field (name "PART NUMBER") "XFMR_MINI-CIRCUITS_TC4-1T+")
        (field (name "MANUFACTURER") "MINI-CIRCUITS")
        (field (name "MANUFACTURER PART NUMBER") "TC4-1T+")
        (field (name "AUTHOR") "GK")
      )
      (libsource (lib "") (part "XFMR_MINI-CIRCUITS_TC4-1T+_1"))
    )
    (comp (ref "TR5")
      (value "1:4")
      (footprint "XFMR_MINI-CIRCUITS_AT224")
      (description "50 Ohms 0.5 to 300 MHz RF Transformer")
      (fields
        (field (name "PART NUMBER") "XFMR_MINI-CIRCUITS_TC4-1T+")
        (field (name "MANUFACTURER") "MINI-CIRCUITS")
        (field (name "MANUFACTURER PART NUMBER") "TC4-1T+")
        (field (name "AUTHOR") "GK")
      )
      (libsource (lib "Inductors_Transformers") (part "XFMR_MINI-CIRCUITS_TC4-1T+"))
    )
    (comp (ref "TR7")
      (value "1:2")
      (footprint "XFMR_MINI-CIRCUITS_AT1521")
      (description "50 Ohms 10 to 700MHz RF Transformer")
      (fields
        (field (name "PART NUMBER") "XFMR_MINI-CIRCUITS_TC2-72T+")
        (field (name "MANUFACTURER") "MINI-CIRCUITS")
        (field (name "MANUFACTURER PART NUMBER") "TC2-72T+")
        (field (name "AUTHOR") "CERN DEM BC")
      )
      (libsource (lib "Inductors & Transformers") (part "XFMR_MINI-CIRCUITS_TC2-72T+"))
    )
    (comp (ref "TR8")
      (value "1:4")
      (footprint "XFMR_MINI-CIRCUITS_AT224")
      (description "50 Ohms 0.5 to 300 MHz RF Transformer")
      (fields
        (field (name "PART NUMBER") "XFMR_MINI-CIRCUITS_TC4-1T+")
        (field (name "MANUFACTURER") "MINI-CIRCUITS")
        (field (name "MANUFACTURER PART NUMBER") "TC4-1T+")
        (field (name "AUTHOR") "GK")
      )
      (libsource (lib "Inductors_Transformers") (part "XFMR_MINI-CIRCUITS_TC4-1T+"))
    )
    (comp (ref "TR9")
      (value "1:2")
      (footprint "XFMR_MINI-CIRCUITS_AT1521")
      (description "50 Ohms 10 to 700MHz RF Transformer")
      (fields
        (field (name "PART NUMBER") "XFMR_MINI-CIRCUITS_TC2-72T+")
        (field (name "MANUFACTURER") "MINI-CIRCUITS")
        (field (name "MANUFACTURER PART NUMBER") "TC2-72T+")
        (field (name "AUTHOR") "CERN DEM BC")
      )
      (libsource (lib "Inductors & Transformers") (part "XFMR_MINI-CIRCUITS_TC2-72T+"))
    )
    (comp (ref "TR10")
      (value "1:2")
      (footprint "XFMR_MINI-CIRCUITS_AT1521")
      (description "50 Ohms 10 to 700MHz RF Transformer")
      (fields
        (field (name "PART NUMBER") "XFMR_MINI-CIRCUITS_TC2-72T+")
        (field (name "MANUFACTURER") "MINI-CIRCUITS")
        (field (name "MANUFACTURER PART NUMBER") "TC2-72T+")
        (field (name "AUTHOR") "CERN DEM BC")
      )
      (libsource (lib "Inductors & Transformers") (part "XFMR_MINI-CIRCUITS_TC2-72T+"))
    )
    (comp (ref "TR11")
      (value "1:2")
      (footprint "XFMR_MINI-CIRCUITS_AT1521")
      (description "50 Ohms 10 to 700MHz RF Transformer")
      (fields
        (field (name "PART NUMBER") "XFMR_MINI-CIRCUITS_TC2-72T+")
        (field (name "MANUFACTURER") "MINI-CIRCUITS")
        (field (name "MANUFACTURER PART NUMBER") "TC2-72T+")
        (field (name "AUTHOR") "CERN DEM BC")
      )
      (libsource (lib "Inductors & Transformers") (part "XFMR_MINI-CIRCUITS_TC2-72T+"))
    )
    (comp (ref "U1")
      (value "DAC34H84IZAY")
      (footprint "TI-ZAY196")
      (description "Quad-Channel, 16-Bit, 1.5 GSPS DAC, -40 to 85 degC, 196-pin BGA (ZAY196), Green (RoHS & no Sb/Br)")
      (fields (field (name "MANUFACTURER") "Texas Instruments"))
      (libsource (lib "Altium Content Vault") (part "TI-DAC34H_SH84-ZAY196"))
    )
  )
  (nets
    (net (code "4") (name "/DACOUTA_N") (class "Default")
      (node (ref "C383") (pin "2") (pinfunction "2_2") (pintype "passive"))
      (node (ref "R17") (pin "1") (pinfunction "1_1") (pintype "passive"))
    )
    (net (code "5") (name "/DACOUTA_P") (class "Default")
      (node (ref "C382") (pin "2") (pinfunction "2_2") (pintype "passive"))
      (node (ref "R3") (pin "1") (pinfunction "1_1") (pintype "passive"))
    )
    (net (code "6") (name "/DACOUTB_N") (class "Default")
      (node (ref "C385") (pin "2") (pinfunction "2_2") (pintype "passive"))
      (node (ref "R228") (pin "1") (pinfunction "1_1") (pintype "passive"))
    )
    (net (code "7") (name "/DACOUTB_P") (class "Default")
      (node (ref "C384") (pin "2") (pinfunction "2_2") (pintype "passive"))
      (node (ref "R227") (pin "1") (pinfunction "1_1") (pintype "passive"))
    )
    (net (code "8") (name "/DACOUTC_N") (class "Default")
      (node (ref "C387") (pin "2") (pinfunction "2_2") (pintype "passive"))
      (node (ref "R69") (pin "1") (pinfunction "1_1") (pintype "passive"))
    )
    (net (code "9") (name "/DACOUTC_P") (class "Default")
      (node (ref "C386") (pin "2") (pinfunction "2_2") (pintype "passive"))
      (node (ref "R68") (pin "1") (pinfunction "1_1") (pintype "passive"))
    )
    (net (code "10") (name "/DACOUTD_N") (class "Default")
      (node (ref "C389") (pin "2") (pinfunction "2_2") (pintype "passive"))
      (node (ref "R230") (pin "1") (pinfunction "1_1") (pintype "passive"))
    )
    (net (code "11") (name "/DACOUTD_P") (class "Default")
      (node (ref "C388") (pin "2") (pinfunction "2_2") (pintype "passive"))
      (node (ref "R229") (pin "1") (pinfunction "1_1") (pintype "passive"))
    )
    (net (code "12") (name "/DAC_ALARM") (class "Default")
      (node (ref "U1") (pin "N12") (pinfunction "ALARM_N12") (pintype "tri_state"))
    )
    (net (code "13") (name "/DAC_CLK_N") (class "Default")
      (node (ref "R88") (pin "2") (pinfunction "2_2") (pintype "passive"))
      (node (ref "U1") (pin "A11") (pinfunction "DACCLKN_A11") (pintype "input"))
    )
    (net (code "14") (name "/DAC_CLK_P") (class "Default")
      (node (ref "R88") (pin "1") (pinfunction "1_1") (pintype "passive"))
      (node (ref "U1") (pin "A12") (pinfunction "DACCLKP_A12") (pintype "input"))
    )
    (net (code "15") (name "/DAC_OUT0") (class "Default")
      (node (ref "R252") (pin "1") (pinfunction "1_1") (pintype "passive"))
    )
    (net (code "16") (name "/DAC_OUT1") (class "Default")
      (node (ref "R249") (pin "1") (pinfunction "1_1") (pintype "passive"))
    )
    (net (code "17") (name "/DAC_OUTA_N") (class "Default")
      (node (ref "R2") (pin "2") (pinfunction "2_2") (pintype "passive"))
      (node (ref "R269") (pin "1") (pinfunction "1_1") (pintype "passive"))
      (node (ref "R39") (pin "2") (pinfunction "2_2") (pintype "passive"))
      (node (ref "TR3") (pin "1") (pinfunction "SDOT_1") (pintype "passive"))
      (node (ref "TR7") (pin "1") (pinfunction "SDOT_1") (pintype "passive"))
    )
    (net (code "18") (name "/DAC_OUTA_P") (class "Default")
      (node (ref "R248") (pin "1") (pinfunction "1_1") (pintype "passive"))
      (node (ref "R37") (pin "2") (pinfunction "2_2") (pintype "passive"))
      (node (ref "R59") (pin "2") (pinfunction "2_2") (pintype "passive"))
      (node (ref "TR3") (pin "3") (pinfunction "S_3") (pintype "passive"))
      (node (ref "TR7") (pin "3") (pinfunction "S_3") (pintype "passive"))
    )
    (net (code "19") (name "/DAC_OUTB_N") (class "Default")
      (node (ref "R271") (pin "1") (pinfunction "1_1") (pintype "passive"))
      (node (ref "R50") (pin "2") (pinfunction "2_2") (pintype "passive"))
      (node (ref "R54") (pin "2") (pinfunction "2_2") (pintype "passive"))
      (node (ref "TR8") (pin "3") (pinfunction "S_3") (pintype "passive"))
      (node (ref "TR9") (pin "3") (pinfunction "S_3") (pintype "passive"))
    )
    (net (code "20") (name "/DAC_OUTB_P") (class "Default")
      (node (ref "R270") (pin "1") (pinfunction "1_1") (pintype "passive"))
      (node (ref "R32") (pin "2") (pinfunction "2_2") (pintype "passive"))
      (node (ref "R40") (pin "2") (pinfunction "2_2") (pintype "passive"))
      (node (ref "TR8") (pin "1") (pinfunction "SDOT_1") (pintype "passive"))
      (node (ref "TR9") (pin "1") (pinfunction "SDOT_1") (pintype "passive"))
    )
    (net (code "21") (name "/DAC_OUTC_N") (class "Default")
      (node (ref "R273") (pin "1") (pinfunction "1_1") (pintype "passive"))
      (node (ref "R66") (pin "2") (pinfunction "2_2") (pintype "passive"))
      (node (ref "R67") (pin "2") (pinfunction "2_2") (pintype "passive"))
      (node (ref "TR10") (pin "1") (pinfunction "SDOT_1") (pintype "passive"))
      (node (ref "TR4") (pin "1") (pinfunction "SDOT_1") (pintype "passive"))
    )
    (net (code "22") (name "/DAC_OUTC_P") (class "Default")
      (node (ref "R272") (pin "1") (pinfunction "1_1") (pintype "passive"))
      (node (ref "R61") (pin "2") (pinfunction "2_2") (pintype "passive"))
      (node (ref "R62") (pin "2") (pinfunction "2_2") (pintype "passive"))
      (node (ref "TR10") (pin "3") (pinfunction "S_3") (pintype "passive"))
      (node (ref "TR4") (pin "3") (pinfunction "S_3") (pintype "passive"))
    )
    (net (code "23") (name "/DAC_OUTD_N") (class "Default")
      (node (ref "R275") (pin "1") (pinfunction "1_1") (pintype "passive"))
      (node (ref "R85") (pin "2") (pinfunction "2_2") (pintype "passive"))
      (node (ref "R86") (pin "2") (pinfunction "2_2") (pintype "passive"))
      (node (ref "TR11") (pin "3") (pinfunction "S_3") (pintype "passive"))
      (node (ref "TR5") (pin "3") (pinfunction "S_3") (pintype "passive"))
    )
    (net (code "24") (name "/DAC_OUTD_P") (class "Default")
      (node (ref "R274") (pin "1") (pinfunction "1_1") (pintype "passive"))
      (node (ref "R76") (pin "2") (pinfunction "2_2") (pintype "passive"))
      (node (ref "R77") (pin "2") (pinfunction "2_2") (pintype "passive"))
      (node (ref "TR11") (pin "1") (pinfunction "SDOT_1") (pintype "passive"))
      (node (ref "TR5") (pin "1") (pinfunction "SDOT_1") (pintype "passive"))
    )
    (net (code "25") (name "/DAC_RESETB") (class "Default")
      (node (ref "R36") (pin "1") (pinfunction "1_1") (pintype "passive"))
      (node (ref "U1") (pin "N10") (pinfunction "RESETB_N10") (pintype "input"))
    )
    (net (code "26") (name "/DAC_SCLK") (class "Default")
      (node (ref "B9") (pin "1") (pinfunction "1_1") (pintype "bidirectional"))
      (node (ref "U1") (pin "P9") (pinfunction "SCLK_P9") (pintype "input"))
    )
    (net (code "27") (name "/DAC_SDENB") (class "Default")
      (node (ref "B12") (pin "1") (pinfunction "1_1") (pintype "bidirectional"))
      (node (ref "U1") (pin "P10") (pinfunction "SDENB_P10") (pintype "input"))
    )
    (net (code "28") (name "/DAC_SDIO") (class "Default")
      (node (ref "B10") (pin "1") (pinfunction "1_1") (pintype "bidirectional"))
      (node (ref "U1") (pin "P11") (pinfunction "SDIO_P11") (pintype "bidirectional"))
    )
    (net (code "29") (name "/DAC_SDO") (class "Default")
      (node (ref "B11") (pin "1") (pinfunction "1_1") (pintype "bidirectional"))
      (node (ref "U1") (pin "P12") (pinfunction "SDO_P12") (pintype "tri_state"))
    )
    (net (code "30") (name "/DAC_SLEEP") (class "Default")
      (node (ref "R231") (pin "1") (pinfunction "1_1") (pintype "passive"))
      (node (ref "U1") (pin "N11") (pinfunction "SLEEP_N11") (pintype "input"))
    )
    (net (code "31") (name "/DAC_TXENA") (class "Default")
      (node (ref "B13") (pin "1") (pinfunction "1_1") (pintype "bidirectional"))
      (node (ref "U1") (pin "N9") (pinfunction "TXENA_N9") (pintype "input"))
    )
    (net (code "32") (name "/DATA_CLK_N") (class "Default")
      (node (ref "U1") (pin "G1") (pinfunction "DATACLKN_G1") (pintype "input"))
    )
    (net (code "33") (name "/DATA_CLK_P") (class "Default")
      (node (ref "U1") (pin "G2") (pinfunction "DATACLKP_G2") (pintype "input"))
    )
    (net (code "34") (name "/IOUTA_N") (class "Default")
      (node (ref "C136") (pin "1") (pinfunction "1_1") (pintype "passive"))
      (node (ref "L12") (pin "1") (pinfunction "1_1") (pintype "passive"))
      (node (ref "R12") (pin "1") (pinfunction "1_1") (pintype "passive"))
      (node (ref "R258") (pin "1") (pinfunction "1_1") (pintype "passive"))
      (node (ref "U1") (pin "C14") (pinfunction "IOUTAN_C14") (pintype "output"))
    )
    (net (code "35") (name "/IOUTA_P") (class "Default")
      (node (ref "C136") (pin "2") (pinfunction "2_2") (pintype "passive"))
      (node (ref "L6") (pin "1") (pinfunction "1_1") (pintype "passive"))
      (node (ref "R11") (pin "1") (pinfunction "1_1") (pintype "passive"))
      (node (ref "R184") (pin "1") (pinfunction "1_1") (pintype "passive"))
      (node (ref "U1") (pin "B14") (pinfunction "IOUTAP_B14") (pintype "output"))
    )
    (net (code "36") (name "/IOUTB_N") (class "Default")
      (node (ref "C49") (pin "1") (pinfunction "1_1") (pintype "passive"))
      (node (ref "L23") (pin "1") (pinfunction "1_1") (pintype "passive"))
      (node (ref "R15") (pin "1") (pinfunction "1_1") (pintype "passive"))
      (node (ref "R264") (pin "1") (pinfunction "1_1") (pintype "passive"))
      (node (ref "U1") (pin "E14") (pinfunction "IOUTBN_E14") (pintype "output"))
    )
    (net (code "37") (name "/IOUTB_P") (class "Default")
      (node (ref "C49") (pin "2") (pinfunction "2_2") (pintype "passive"))
      (node (ref "L1") (pin "1") (pinfunction "1_1") (pintype "passive"))
      (node (ref "R13") (pin "1") (pinfunction "1_1") (pintype "passive"))
      (node (ref "R263") (pin "1") (pinfunction "1_1") (pintype "passive"))
      (node (ref "U1") (pin "F14") (pinfunction "IOUTBP_F14") (pintype "output"))
    )
    (net (code "38") (name "/IOUTC_N") (class "Default")
      (node (ref "C141") (pin "1") (pinfunction "1_1") (pintype "passive"))
      (node (ref "L39") (pin "1") (pinfunction "1_1") (pintype "passive"))
      (node (ref "R21") (pin "1") (pinfunction "1_1") (pintype "passive"))
      (node (ref "R266") (pin "1") (pinfunction "1_1") (pintype "passive"))
      (node (ref "U1") (pin "K14") (pinfunction "IOUTCN_K14") (pintype "output"))
    )
    (net (code "39") (name "/IOUTC_P") (class "Default")
      (node (ref "C141") (pin "2") (pinfunction "2_2") (pintype "passive"))
      (node (ref "L36") (pin "1") (pinfunction "1_1") (pintype "passive"))
      (node (ref "R16") (pin "1") (pinfunction "1_1") (pintype "passive"))
      (node (ref "R265") (pin "1") (pinfunction "1_1") (pintype "passive"))
      (node (ref "U1") (pin "J14") (pinfunction "IOUTCP_J14") (pintype "output"))
    )
    (net (code "40") (name "/IOUTD_N") (class "Default")
      (node (ref "C379") (pin "1") (pinfunction "1_1") (pintype "passive"))
      (node (ref "L55") (pin "1") (pinfunction "1_1") (pintype "passive"))
      (node (ref "R268") (pin "1") (pinfunction "1_1") (pintype "passive"))
      (node (ref "R31") (pin "1") (pinfunction "1_1") (pintype "passive"))
      (node (ref "U1") (pin "M14") (pinfunction "IOUTDN_M14") (pintype "output"))
    )
    (net (code "41") (name "/IOUTD_P") (class "Default")
      (node (ref "C379") (pin "2") (pinfunction "2_2") (pintype "passive"))
      (node (ref "L53") (pin "1") (pinfunction "1_1") (pintype "passive"))
      (node (ref "R24") (pin "1") (pinfunction "1_1") (pintype "passive"))
      (node (ref "R267") (pin "1") (pinfunction "1_1") (pintype "passive"))
      (node (ref "U1") (pin "N14") (pinfunction "IOUTDP_N14") (pintype "output"))
    )
    (net (code "42") (name "/ISTR_PARITYAB_N") (class "Default")
      (node (ref "U1") (pin "H1") (pinfunction "ISTRN/PARITYABN_H1") (pintype "input"))
    )
    (net (code "43") (name "/ISTR_PARITYAB_P") (class "Default")
      (node (ref "U1") (pin "H2") (pinfunction "ISTRP/PARITYABP_H2") (pintype "input"))
    )
    (net (code "44") (name "/LVDSA0_N") (class "Default")
      (node (ref "U1") (pin "G3") (pinfunction "DAB0N_(LSB)_G3") (pintype "input"))
    )
    (net (code "45") (name "/LVDSA0_P") (class "Default")
      (node (ref "U1") (pin "G4") (pinfunction "DAB0P_(LSB)_G4") (pintype "input"))
    )
    (net (code "46") (name "/LVDSA1_N") (class "Default")
      (node (ref "U1") (pin "F1") (pinfunction "DAB1N_F1") (pintype "input"))
    )
    (net (code "47") (name "/LVDSA1_P") (class "Default")
      (node (ref "U1") (pin "F2") (pinfunction "DAB1P_F2") (pintype "input"))
    )
    (net (code "48") (name "/LVDSA2_N") (class "Default")
      (node (ref "U1") (pin "F3") (pinfunction "DAB2N_F3") (pintype "input"))
    )
    (net (code "49") (name "/LVDSA2_P") (class "Default")
      (node (ref "U1") (pin "F4") (pinfunction "DAB2P_F4") (pintype "input"))
    )
    (net (code "50") (name "/LVDSA3_N") (class "Default")
      (node (ref "U1") (pin "E1") (pinfunction "DAB3N_E1") (pintype "input"))
    )
    (net (code "51") (name "/LVDSA3_P") (class "Default")
      (node (ref "U1") (pin "E2") (pinfunction "DAB3P_E2") (pintype "input"))
    )
    (net (code "52") (name "/LVDSA4_N") (class "Default")
      (node (ref "U1") (pin "E3") (pinfunction "DAB4N_E3") (pintype "input"))
    )
    (net (code "53") (name "/LVDSA4_P") (class "Default")
      (node (ref "U1") (pin "E4") (pinfunction "DAB4P_E4") (pintype "input"))
    )
    (net (code "54") (name "/LVDSA5_N") (class "Default")
      (node (ref "U1") (pin "D1") (pinfunction "DAB5N_D1") (pintype "input"))
    )
    (net (code "55") (name "/LVDSA5_P") (class "Default")
      (node (ref "U1") (pin "D2") (pinfunction "DAB5P_D2") (pintype "input"))
    )
    (net (code "56") (name "/LVDSA6_N") (class "Default")
      (node (ref "U1") (pin "D3") (pinfunction "DAB6N_D3") (pintype "input"))
    )
    (net (code "57") (name "/LVDSA6_P") (class "Default")
      (node (ref "U1") (pin "D4") (pinfunction "DAB6P_D4") (pintype "input"))
    )
    (net (code "58") (name "/LVDSA7_N") (class "Default")
      (node (ref "U1") (pin "C1") (pinfunction "DAB7N_C1") (pintype "input"))
    )
    (net (code "59") (name "/LVDSA7_P") (class "Default")
      (node (ref "U1") (pin "C2") (pinfunction "DAB7P_C2") (pintype "input"))
    )
    (net (code "60") (name "/LVDSA8_N") (class "Default")
      (node (ref "U1") (pin "C3") (pinfunction "DAB8N_C3") (pintype "input"))
    )
    (net (code "61") (name "/LVDSA8_P") (class "Default")
      (node (ref "U1") (pin "C4") (pinfunction "DAB8P_C4") (pintype "input"))
    )
    (net (code "62") (name "/LVDSA9_N") (class "Default")
      (node (ref "U1") (pin "B1") (pinfunction "DAB9N_B1") (pintype "input"))
    )
    (net (code "63") (name "/LVDSA9_P") (class "Default")
      (node (ref "U1") (pin "A1") (pinfunction "DAB9P_A1") (pintype "input"))
    )
    (net (code "64") (name "/LVDSA10_N") (class "Default")
      (node (ref "U1") (pin "B2") (pinfunction "DAB10N_B2") (pintype "input"))
    )
    (net (code "65") (name "/LVDSA10_P") (class "Default")
      (node (ref "U1") (pin "A2") (pinfunction "DAB10P_A2") (pintype "input"))
    )
    (net (code "66") (name "/LVDSA11_N") (class "Default")
      (node (ref "U1") (pin "B3") (pinfunction "DAB11N_B3") (pintype "input"))
    )
    (net (code "67") (name "/LVDSA11_P") (class "Default")
      (node (ref "U1") (pin "A3") (pinfunction "DAB11P_A3") (pintype "input"))
    )
    (net (code "68") (name "/LVDSA12_N") (class "Default")
      (node (ref "U1") (pin "B4") (pinfunction "DAB12N_B4") (pintype "input"))
    )
    (net (code "69") (name "/LVDSA12_P") (class "Default")
      (node (ref "U1") (pin "A4") (pinfunction "DAB12P_A4") (pintype "input"))
    )
    (net (code "70") (name "/LVDSA13_N") (class "Default")
      (node (ref "U1") (pin "B5") (pinfunction "DAB13N_B5") (pintype "input"))
    )
    (net (code "71") (name "/LVDSA13_P") (class "Default")
      (node (ref "U1") (pin "A5") (pinfunction "DAB13P_A5") (pintype "input"))
    )
    (net (code "72") (name "/LVDSA14_N") (class "Default")
      (node (ref "U1") (pin "B6") (pinfunction "DAB14N_B6") (pintype "input"))
    )
    (net (code "73") (name "/LVDSA14_P") (class "Default")
      (node (ref "U1") (pin "A6") (pinfunction "DAB14P_A6") (pintype "input"))
    )
    (net (code "74") (name "/LVDSA15_N") (class "Default")
      (node (ref "U1") (pin "B7") (pinfunction "DAB15N_(MSB)_B7") (pintype "input"))
    )
    (net (code "75") (name "/LVDSA15_P") (class "Default")
      (node (ref "U1") (pin "A7") (pinfunction "DAB15P_(MSB)_A7") (pintype "input"))
    )
    (net (code "76") (name "/LVDSB0_N") (class "Default")
      (node (ref "U1") (pin "P7") (pinfunction "DCD0N_(LSB)_P7") (pintype "input"))
    )
    (net (code "77") (name "/LVDSB0_P") (class "Default")
      (node (ref "U1") (pin "N7") (pinfunction "DCD0P_(LSB)_N7") (pintype "input"))
    )
    (net (code "78") (name "/LVDSB1_N") (class "Default")
      (node (ref "U1") (pin "P6") (pinfunction "DCD1N_P6") (pintype "input"))
    )
    (net (code "79") (name "/LVDSB1_P") (class "Default")
      (node (ref "U1") (pin "N6") (pinfunction "DCD1P_N6") (pintype "input"))
    )
    (net (code "80") (name "/LVDSB2_N") (class "Default")
      (node (ref "U1") (pin "P5") (pinfunction "DCD2N_P5") (pintype "input"))
    )
    (net (code "81") (name "/LVDSB2_P") (class "Default")
      (node (ref "U1") (pin "N5") (pinfunction "DCD2P_N5") (pintype "input"))
    )
    (net (code "82") (name "/LVDSB3_N") (class "Default")
      (node (ref "U1") (pin "P4") (pinfunction "DCD3N_P4") (pintype "input"))
    )
    (net (code "83") (name "/LVDSB3_P") (class "Default")
      (node (ref "U1") (pin "N4") (pinfunction "DCD3P_N4") (pintype "input"))
    )
    (net (code "84") (name "/LVDSB4_N") (class "Default")
      (node (ref "U1") (pin "P3") (pinfunction "DCD4N_P3") (pintype "input"))
    )
    (net (code "85") (name "/LVDSB4_P") (class "Default")
      (node (ref "U1") (pin "N3") (pinfunction "DCD4P_N3") (pintype "input"))
    )
    (net (code "86") (name "/LVDSB5_N") (class "Default")
      (node (ref "U1") (pin "P2") (pinfunction "DCD5N_P2") (pintype "input"))
    )
    (net (code "87") (name "/LVDSB5_P") (class "Default")
      (node (ref "U1") (pin "N2") (pinfunction "DCD5P_N2") (pintype "input"))
    )
    (net (code "88") (name "/LVDSB6_N") (class "Default")
      (node (ref "U1") (pin "P1") (pinfunction "DCD6N_P1") (pintype "input"))
    )
    (net (code "89") (name "/LVDSB6_P") (class "Default")
      (node (ref "U1") (pin "N1") (pinfunction "DCD6P_N1") (pintype "input"))
    )
    (net (code "90") (name "/LVDSB7_N") (class "Default")
      (node (ref "U1") (pin "M1") (pinfunction "DCD7N_M1") (pintype "input"))
    )
    (net (code "91") (name "/LVDSB7_P") (class "Default")
      (node (ref "U1") (pin "M2") (pinfunction "DCD7P_M2") (pintype "input"))
    )
    (net (code "92") (name "/LVDSB8_N") (class "Default")
      (node (ref "U1") (pin "M3") (pinfunction "DCD8N_M3") (pintype "input"))
    )
    (net (code "93") (name "/LVDSB8_P") (class "Default")
      (node (ref "U1") (pin "M4") (pinfunction "DCD8P_M4") (pintype "input"))
    )
    (net (code "94") (name "/LVDSB9_N") (class "Default")
      (node (ref "U1") (pin "L1") (pinfunction "DCD9N_L1") (pintype "input"))
    )
    (net (code "95") (name "/LVDSB9_P") (class "Default")
      (node (ref "U1") (pin "L2") (pinfunction "DCD9P_L2") (pintype "input"))
    )
    (net (code "96") (name "/LVDSB10_N") (class "Default")
      (node (ref "U1") (pin "L3") (pinfunction "DCD10N_L3") (pintype "input"))
    )
    (net (code "97") (name "/LVDSB10_P") (class "Default")
      (node (ref "U1") (pin "L4") (pinfunction "DCD10P_L4") (pintype "input"))
    )
    (net (code "98") (name "/LVDSB11_N") (class "Default")
      (node (ref "U1") (pin "K1") (pinfunction "DCD11N_K1") (pintype "input"))
    )
    (net (code "99") (name "/LVDSB11_P") (class "Default")
      (node (ref "U1") (pin "K2") (pinfunction "DCD11P_K2") (pintype "input"))
    )
    (net (code "100") (name "/LVDSB12_N") (class "Default")
      (node (ref "U1") (pin "K3") (pinfunction "DCD12N_K3") (pintype "input"))
    )
    (net (code "101") (name "/LVDSB12_P") (class "Default")
      (node (ref "U1") (pin "K4") (pinfunction "DCD12P_K4") (pintype "input"))
    )
    (net (code "102") (name "/LVDSB13_N") (class "Default")
      (node (ref "U1") (pin "J1") (pinfunction "DCD13N_J1") (pintype "input"))
    )
    (net (code "103") (name "/LVDSB13_P") (class "Default")
      (node (ref "U1") (pin "J2") (pinfunction "DCD13P_J2") (pintype "input"))
    )
    (net (code "104") (name "/LVDSB14_N") (class "Default")
      (node (ref "U1") (pin "J3") (pinfunction "DCD14N_J3") (pintype "input"))
    )
    (net (code "105") (name "/LVDSB14_P") (class "Default")
      (node (ref "U1") (pin "J4") (pinfunction "DCD14P_J4") (pintype "input"))
    )
    (net (code "106") (name "/LVDSB15_N") (class "Default")
      (node (ref "U1") (pin "H3") (pinfunction "DCD15N_(MSB)_H3") (pintype "input"))
    )
    (net (code "107") (name "/LVDSB15_P") (class "Default")
      (node (ref "U1") (pin "H4") (pinfunction "DCD15P_(MSB)_H4") (pintype "input"))
    )
    (net (code "108") (name "/OSTR_N") (class "Default")
      (node (ref "C360") (pin "1") (pinfunction "1_1") (pintype "passive"))
    )
    (net (code "109") (name "/OSTR_P") (class "Default")
      (node (ref "C363") (pin "1") (pinfunction "1_1") (pintype "passive"))
    )
    (net (code "110") (name "/PARITYCD_N") (class "Default")
      (node (ref "U1") (pin "P8") (pinfunction "PARITYCDN_P8") (pintype "input"))
    )
    (net (code "111") (name "/PARITYCD_P") (class "Default")
      (node (ref "U1") (pin "N8") (pinfunction "PARITYCDP_N8") (pintype "input"))
    )
    (net (code "112") (name "/SYNC_N") (class "Default")
      (node (ref "U1") (pin "B8") (pinfunction "SYNCN_B8") (pintype "input"))
    )
    (net (code "113") (name "/SYNC_P") (class "Default")
      (node (ref "U1") (pin "A8") (pinfunction "SYNCP_A8") (pintype "input"))
    )
    (net (code "117") (name "GND") (class "Default")
      (node (ref "C145") (pin "1") (pinfunction "1_1") (pintype "passive"))
      (node (ref "C146") (pin "1") (pinfunction "1_1") (pintype "passive"))
      (node (ref "C25") (pin "2") (pinfunction "2_2") (pintype "passive"))
      (node (ref "C32") (pin "2") (pinfunction "2_2") (pintype "passive"))
      (node (ref "J13") (pin "2") (pinfunction "2_2") (pintype "bidirectional"))
      (node (ref "J15") (pin "2") (pinfunction "2_2") (pintype "bidirectional"))
      (node (ref "R11") (pin "2") (pinfunction "2_2") (pintype "passive"))
      (node (ref "R12") (pin "2") (pinfunction "2_2") (pintype "passive"))
      (node (ref "R13") (pin "2") (pinfunction "2_2") (pintype "passive"))
      (node (ref "R15") (pin "2") (pinfunction "2_2") (pintype "passive"))
      (node (ref "R16") (pin "2") (pinfunction "2_2") (pintype "passive"))
      (node (ref "R184") (pin "2") (pinfunction "2_2") (pintype "passive"))
      (node (ref "R21") (pin "2") (pinfunction "2_2") (pintype "passive"))
      (node (ref "R24") (pin "2") (pinfunction "2_2") (pintype "passive"))
      (node (ref "R250") (pin "1") (pinfunction "1_1") (pintype "passive"))
      (node (ref "R251") (pin "1") (pinfunction "1_1") (pintype "passive"))
      (node (ref "R253") (pin "1") (pinfunction "1_1") (pintype "passive"))
      (node (ref "R254") (pin "1") (pinfunction "1_1") (pintype "passive"))
      (node (ref "R258") (pin "2") (pinfunction "2_2") (pintype "passive"))
      (node (ref "R263") (pin "2") (pinfunction "2_2") (pintype "passive"))
      (node (ref "R264") (pin "2") (pinfunction "2_2") (pintype "passive"))
      (node (ref "R265") (pin "2") (pinfunction "2_2") (pintype "passive"))
      (node (ref "R266") (pin "2") (pinfunction "2_2") (pintype "passive"))
      (node (ref "R267") (pin "2") (pinfunction "2_2") (pintype "passive"))
      (node (ref "R268") (pin "2") (pinfunction "2_2") (pintype "passive"))
      (node (ref "R31") (pin "2") (pinfunction "2_2") (pintype "passive"))
      (node (ref "R35") (pin "2") (pinfunction "2_2") (pintype "passive"))
      (node (ref "R36") (pin "2") (pinfunction "2_2") (pintype "passive"))
      (node (ref "TR10") (pin "2") (pinfunction "NC_2") (pintype "passive"))
      (node (ref "TR11") (pin "2") (pinfunction "NC_2") (pintype "passive"))
      (node (ref "TR3") (pin "2") (pinfunction "SCT_2") (pintype "passive"))
      (node (ref "TR4") (pin "2") (pinfunction "SCT_2") (pintype "passive"))
      (node (ref "TR5") (pin "2") (pinfunction "SCT_2") (pintype "passive"))
      (node (ref "TR7") (pin "2") (pinfunction "NC_2") (pintype "passive"))
      (node (ref "TR8") (pin "2") (pinfunction "SCT_2") (pintype "passive"))
      (node (ref "TR9") (pin "2") (pinfunction "NC_2") (pintype "passive"))
    )
    (net (code "118") (name "Net-(C32-Pad1)") (class "Default")
      (node (ref "C32") (pin "1") (pinfunction "1_1") (pintype "passive"))
      (node (ref "R232") (pin "2") (pinfunction "2_2") (pintype "passive"))
    )
    (net (code "119") (name "Net-(C36-Pad1)") (class "Default")
      (node (ref "C36") (pin "1") (pinfunction "1_1") (pintype "passive"))
      (node (ref "L30") (pin "2") (pinfunction "2_2") (pintype "passive"))
      (node (ref "R269") (pin "2") (pinfunction "2_2") (pintype "passive"))
      (node (ref "R39") (pin "1") (pinfunction "1_1") (pintype "passive"))
    )
    (net (code "120") (name "Net-(C36-Pad2)") (class "Default")
      (node (ref "C36") (pin "2") (pinfunction "2_2") (pintype "passive"))
      (node (ref "L28") (pin "2") (pinfunction "2_2") (pintype "passive"))
      (node (ref "R248") (pin "2") (pinfunction "2_2") (pintype "passive"))
      (node (ref "R37") (pin "1") (pinfunction "1_1") (pintype "passive"))
    )
    (net (code "121") (name "Net-(C137-Pad1)") (class "Default")
      (node (ref "C137") (pin "1") (pinfunction "1_1") (pintype "passive"))
      (node (ref "L23") (pin "2") (pinfunction "2_2") (pintype "passive"))
      (node (ref "L32") (pin "1") (pinfunction "1_1") (pintype "passive"))
    )
    (net (code "122") (name "Net-(C137-Pad2)") (class "Default")
      (node (ref "C137") (pin "2") (pinfunction "2_2") (pintype "passive"))
      (node (ref "L1") (pin "2") (pinfunction "2_2") (pintype "passive"))
      (node (ref "L21") (pin "1") (pinfunction "1_1") (pintype "passive"))
    )
    (net (code "123") (name "Net-(C140-Pad1)") (class "Default")
      (node (ref "C140") (pin "1") (pinfunction "1_1") (pintype "passive"))
      (node (ref "L32") (pin "2") (pinfunction "2_2") (pintype "passive"))
      (node (ref "R271") (pin "2") (pinfunction "2_2") (pintype "passive"))
      (node (ref "R54") (pin "1") (pinfunction "1_1") (pintype "passive"))
    )
    (net (code "124") (name "Net-(C140-Pad2)") (class "Default")
      (node (ref "C140") (pin "2") (pinfunction "2_2") (pintype "passive"))
      (node (ref "L21") (pin "2") (pinfunction "2_2") (pintype "passive"))
      (node (ref "R270") (pin "2") (pinfunction "2_2") (pintype "passive"))
      (node (ref "R40") (pin "1") (pinfunction "1_1") (pintype "passive"))
    )
    (net (code "125") (name "Net-(C146-Pad2)") (class "Default")
      (node (ref "C146") (pin "2") (pinfunction "2_2") (pintype "passive"))
      (node (ref "R232") (pin "1") (pinfunction "1_1") (pintype "passive"))
      (node (ref "R63") (pin "1") (pinfunction "1_1") (pintype "passive"))
    )
    (net (code "126") (name "Net-(C151-Pad1)") (class "Default")
      (node (ref "C151") (pin "1") (pinfunction "1_1") (pintype "passive"))
      (node (ref "L39") (pin "2") (pinfunction "2_2") (pintype "passive"))
      (node (ref "L40") (pin "1") (pinfunction "1_1") (pintype "passive"))
    )
    (net (code "127") (name "Net-(C151-Pad2)") (class "Default")
      (node (ref "C151") (pin "2") (pinfunction "2_2") (pintype "passive"))
      (node (ref "L36") (pin "2") (pinfunction "2_2") (pintype "passive"))
      (node (ref "L37") (pin "1") (pinfunction "1_1") (pintype "passive"))
    )
    (net (code "128") (name "Net-(C152-Pad1)") (class "Default")
      (node (ref "C152") (pin "1") (pinfunction "1_1") (pintype "passive"))
      (node (ref "L40") (pin "2") (pinfunction "2_2") (pintype "passive"))
      (node (ref "R273") (pin "2") (pinfunction "2_2") (pintype "passive"))
      (node (ref "R67") (pin "1") (pinfunction "1_1") (pintype "passive"))
    )
    (net (code "129") (name "Net-(C152-Pad2)") (class "Default")
      (node (ref "C152") (pin "2") (pinfunction "2_2") (pintype "passive"))
      (node (ref "L37") (pin "2") (pinfunction "2_2") (pintype "passive"))
      (node (ref "R272") (pin "2") (pinfunction "2_2") (pintype "passive"))
      (node (ref "R61") (pin "1") (pinfunction "1_1") (pintype "passive"))
    )
    (net (code "130") (name "Net-(C378-Pad1)") (class "Default")
      (node (ref "C378") (pin "1") (pinfunction "1_1") (pintype "passive"))
      (node (ref "L12") (pin "2") (pinfunction "2_2") (pintype "passive"))
      (node (ref "L30") (pin "1") (pinfunction "1_1") (pintype "passive"))
    )
    (net (code "131") (name "Net-(C378-Pad2)") (class "Default")
      (node (ref "C378") (pin "2") (pinfunction "2_2") (pintype "passive"))
      (node (ref "L28") (pin "1") (pinfunction "1_1") (pintype "passive"))
      (node (ref "L6") (pin "2") (pinfunction "2_2") (pintype "passive"))
    )
    (net (code "132") (name "Net-(C380-Pad1)") (class "Default")
      (node (ref "C380") (pin "1") (pinfunction "1_1") (pintype "passive"))
      (node (ref "L55") (pin "2") (pinfunction "2_2") (pintype "passive"))
      (node (ref "L56") (pin "1") (pinfunction "1_1") (pintype "passive"))
    )
    (net (code "133") (name "Net-(C380-Pad2)") (class "Default")
      (node (ref "C380") (pin "2") (pinfunction "2_2") (pintype "passive"))
      (node (ref "L53") (pin "2") (pinfunction "2_2") (pintype "passive"))
      (node (ref "L54") (pin "1") (pinfunction "1_1") (pintype "passive"))
    )
    (net (code "134") (name "Net-(C381-Pad1)") (class "Default")
      (node (ref "C381") (pin "1") (pinfunction "1_1") (pintype "passive"))
      (node (ref "L56") (pin "2") (pinfunction "2_2") (pintype "passive"))
      (node (ref "R275") (pin "2") (pinfunction "2_2") (pintype "passive"))
      (node (ref "R86") (pin "1") (pinfunction "1_1") (pintype "passive"))
    )
    (net (code "135") (name "Net-(C381-Pad2)") (class "Default")
      (node (ref "C381") (pin "2") (pinfunction "2_2") (pintype "passive"))
      (node (ref "L54") (pin "2") (pinfunction "2_2") (pintype "passive"))
      (node (ref "R274") (pin "2") (pinfunction "2_2") (pintype "passive"))
      (node (ref "R76") (pin "1") (pinfunction "1_1") (pintype "passive"))
    )
    (net (code "136") (name "Net-(J13-Pad1)") (class "Default")
      (node (ref "J13") (pin "1") (pinfunction "1_1") (pintype "bidirectional"))
      (node (ref "R246") (pin "1") (pinfunction "1_1") (pintype "passive"))
    )
    (net (code "137") (name "Net-(J15-Pad1)") (class "Default")
      (node (ref "J15") (pin "1") (pinfunction "1_1") (pintype "bidirectional"))
      (node (ref "R247") (pin "1") (pinfunction "1_1") (pintype "passive"))
    )
    (net (code "138") (name "Net-(R34-Pad2)") (class "Default")
      (node (ref "R34") (pin "2") (pinfunction "2_2") (pintype "passive"))
      (node (ref "R35") (pin "1") (pinfunction "1_1") (pintype "passive"))
    )
    (net (code "139") (name "Net-(TR3-P)") (class "Default")
      (node (ref "C382") (pin "1") (pinfunction "1_1") (pintype "passive"))
      (node (ref "R249") (pin "2") (pinfunction "2_2") (pintype "passive"))
      (node (ref "R3") (pin "2") (pinfunction "2_2") (pintype "passive"))
      (node (ref "R59") (pin "1") (pinfunction "1_1") (pintype "passive"))
      (node (ref "TR3") (pin "4") (pinfunction "P_4") (pintype "passive"))
      (node (ref "TR7") (pin "4") (pinfunction "P_4") (pintype "passive"))
    )
    (net (code "140") (name "Net-(TR3-PDOT)") (class "Default")
      (node (ref "C383") (pin "1") (pinfunction "1_1") (pintype "passive"))
      (node (ref "R17") (pin "2") (pinfunction "2_2") (pintype "passive"))
      (node (ref "R2") (pin "1") (pinfunction "1_1") (pintype "passive"))
      (node (ref "R250") (pin "2") (pinfunction "2_2") (pintype "passive"))
      (node (ref "TR3") (pin "6") (pinfunction "PDOT_6") (pintype "passive"))
      (node (ref "TR7") (pin "6") (pinfunction "PDOT_6") (pintype "passive"))
    )
    (net (code "141") (name "Net-(TR8-P)") (class "Default")
      (node (ref "C385") (pin "1") (pinfunction "1_1") (pintype "passive"))
      (node (ref "R228") (pin "2") (pinfunction "2_2") (pintype "passive"))
      (node (ref "R251") (pin "2") (pinfunction "2_2") (pintype "passive"))
      (node (ref "R50") (pin "1") (pinfunction "1_1") (pintype "passive"))
      (node (ref "TR8") (pin "4") (pinfunction "P_4") (pintype "passive"))
      (node (ref "TR9") (pin "4") (pinfunction "P_4") (pintype "passive"))
    )
    (net (code "142") (name "Net-(TR8-PDOT)") (class "Default")
      (node (ref "C384") (pin "1") (pinfunction "1_1") (pintype "passive"))
      (node (ref "R227") (pin "2") (pinfunction "2_2") (pintype "passive"))
      (node (ref "R246") (pin "2") (pinfunction "2_2") (pintype "passive"))
      (node (ref "R32") (pin "1") (pinfunction "1_1") (pintype "passive"))
      (node (ref "TR8") (pin "6") (pinfunction "PDOT_6") (pintype "passive"))
      (node (ref "TR9") (pin "6") (pinfunction "PDOT_6") (pintype "passive"))
    )
    (net (code "143") (name "Net-(TR10-P)") (class "Default")
      (node (ref "C386") (pin "1") (pinfunction "1_1") (pintype "passive"))
      (node (ref "R252") (pin "2") (pinfunction "2_2") (pintype "passive"))
      (node (ref "R62") (pin "1") (pinfunction "1_1") (pintype "passive"))
      (node (ref "R68") (pin "2") (pinfunction "2_2") (pintype "passive"))
      (node (ref "TR10") (pin "4") (pinfunction "P_4") (pintype "passive"))
      (node (ref "TR4") (pin "4") (pinfunction "P_4") (pintype "passive"))
    )
    (net (code "144") (name "Net-(TR10-PDOT)") (class "Default")
      (node (ref "C387") (pin "1") (pinfunction "1_1") (pintype "passive"))
      (node (ref "R253") (pin "2") (pinfunction "2_2") (pintype "passive"))
      (node (ref "R66") (pin "1") (pinfunction "1_1") (pintype "passive"))
      (node (ref "R69") (pin "2") (pinfunction "2_2") (pintype "passive"))
      (node (ref "TR10") (pin "6") (pinfunction "PDOT_6") (pintype "passive"))
      (node (ref "TR4") (pin "6") (pinfunction "PDOT_6") (pintype "passive"))
    )
    (net (code "145") (name "Net-(TR11-P)") (class "Default")
      (node (ref "C389") (pin "1") (pinfunction "1_1") (pintype "passive"))
      (node (ref "R230") (pin "2") (pinfunction "2_2") (pintype "passive"))
      (node (ref "R254") (pin "2") (pinfunction "2_2") (pintype "passive"))
      (node (ref "R85") (pin "1") (pinfunction "1_1") (pintype "passive"))
      (node (ref "TR11") (pin "4") (pinfunction "P_4") (pintype "passive"))
      (node (ref "TR5") (pin "4") (pinfunction "P_4") (pintype "passive"))
    )
    (net (code "146") (name "Net-(TR11-PDOT)") (class "Default")
      (node (ref "C388") (pin "1") (pinfunction "1_1") (pintype "passive"))
      (node (ref "R229") (pin "2") (pinfunction "2_2") (pintype "passive"))
      (node (ref "R247") (pin "2") (pinfunction "2_2") (pintype "passive"))
      (node (ref "R77") (pin "1") (pinfunction "1_1") (pintype "passive"))
      (node (ref "TR11") (pin "6") (pinfunction "PDOT_6") (pintype "passive"))
      (node (ref "TR5") (pin "6") (pinfunction "PDOT_6") (pintype "passive"))
    )
    (net (code "147") (name "Net-(U1C-BIASJ)") (class "Default")
      (node (ref "R34") (pin "1") (pinfunction "1_1") (pintype "passive"))
      (node (ref "U1") (pin "H12") (pinfunction "BIASJ_H12") (pintype "passive"))
    )
    (net (code "148") (name "Net-(U1C-EXTIO)") (class "Default")
      (node (ref "C145") (pin "2") (pinfunction "2_2") (pintype "passive"))
      (node (ref "C25") (pin "1") (pinfunction "1_1") (pintype "passive"))
      (node (ref "U1") (pin "G12") (pinfunction "EXTIO_G12") (pintype "bidirectional"))
    )
    (net (code "149") (name "Net-(U1C-LPF)") (class "Default")
      (node (ref "R63") (pin "2") (pinfunction "2_2") (pintype "passive"))
      (node (ref "U1") (pin "D12") (pinfunction "LPF_D12") (pintype "passive"))
    )
    (net (code "150") (name "Net-(U1C-OSTRN)") (class "Default")
      (node (ref "C360") (pin "2") (pinfunction "2_2") (pintype "passive"))
      (node (ref "R65") (pin "1") (pinfunction "1_1") (pintype "passive"))
      (node (ref "U1") (pin "B9") (pinfunction "OSTRN_B9") (pintype "input"))
    )
    (net (code "151") (name "Net-(U1C-OSTRP)") (class "Default")
      (node (ref "C363") (pin "2") (pinfunction "2_2") (pintype "passive"))
      (node (ref "R65") (pin "2") (pinfunction "2_2") (pintype "passive"))
      (node (ref "U1") (pin "A9") (pinfunction "OSTRP_A9") (pintype "input"))
    )
    (net (code "152") (name "P3V3") (class "Default")
      (node (ref "R231") (pin "2") (pinfunction "2_2") (pintype "passive"))
    )
    (net (code "153") (name "unconnected-(U1C-TESTMODE-PadL11)") (class "Default")
      (node (ref "U1") (pin "L11") (pinfunction "TESTMODE_L11") (pintype "passive+no_connect"))
    )
  )
)
